# 11_MCU.net
KiCad netlist of a schematic drawn in Altium Designer
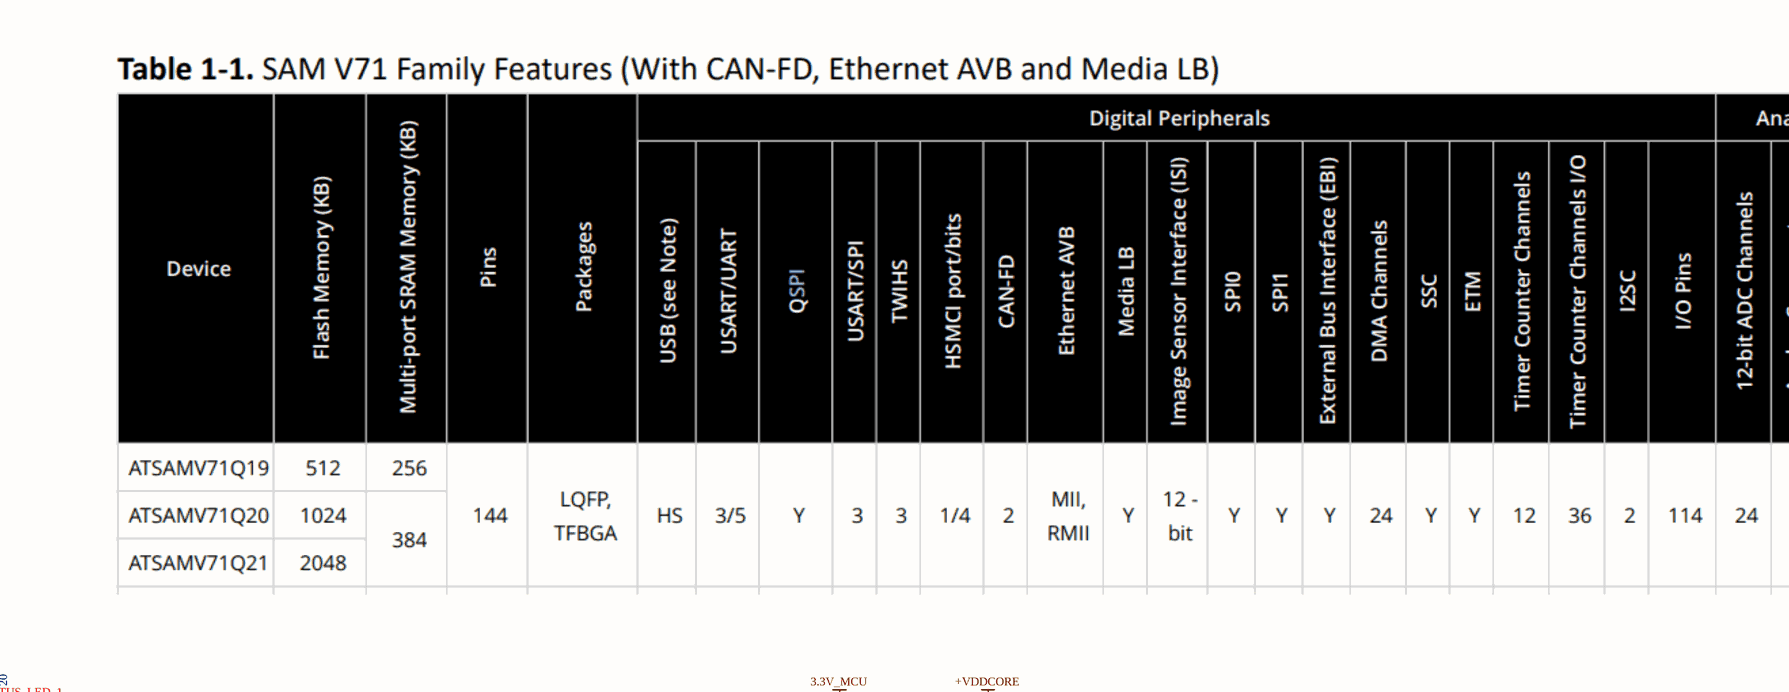
[diagram p0: 11_MCU.SchDoc, top left]
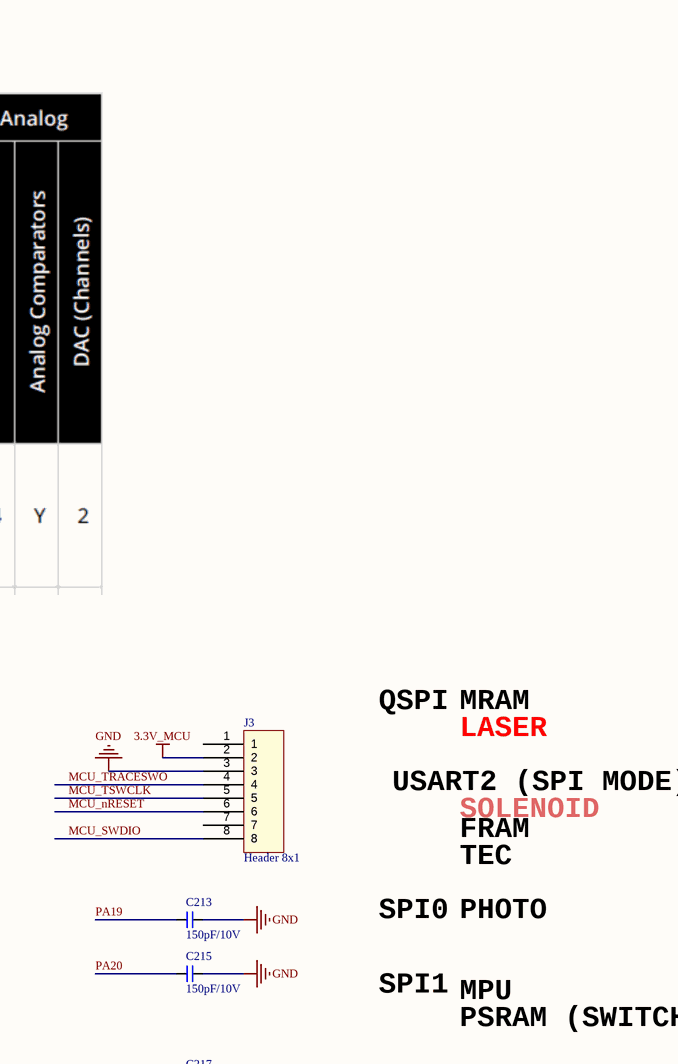
[diagram p1: 11_MCU.SchDoc, top right]
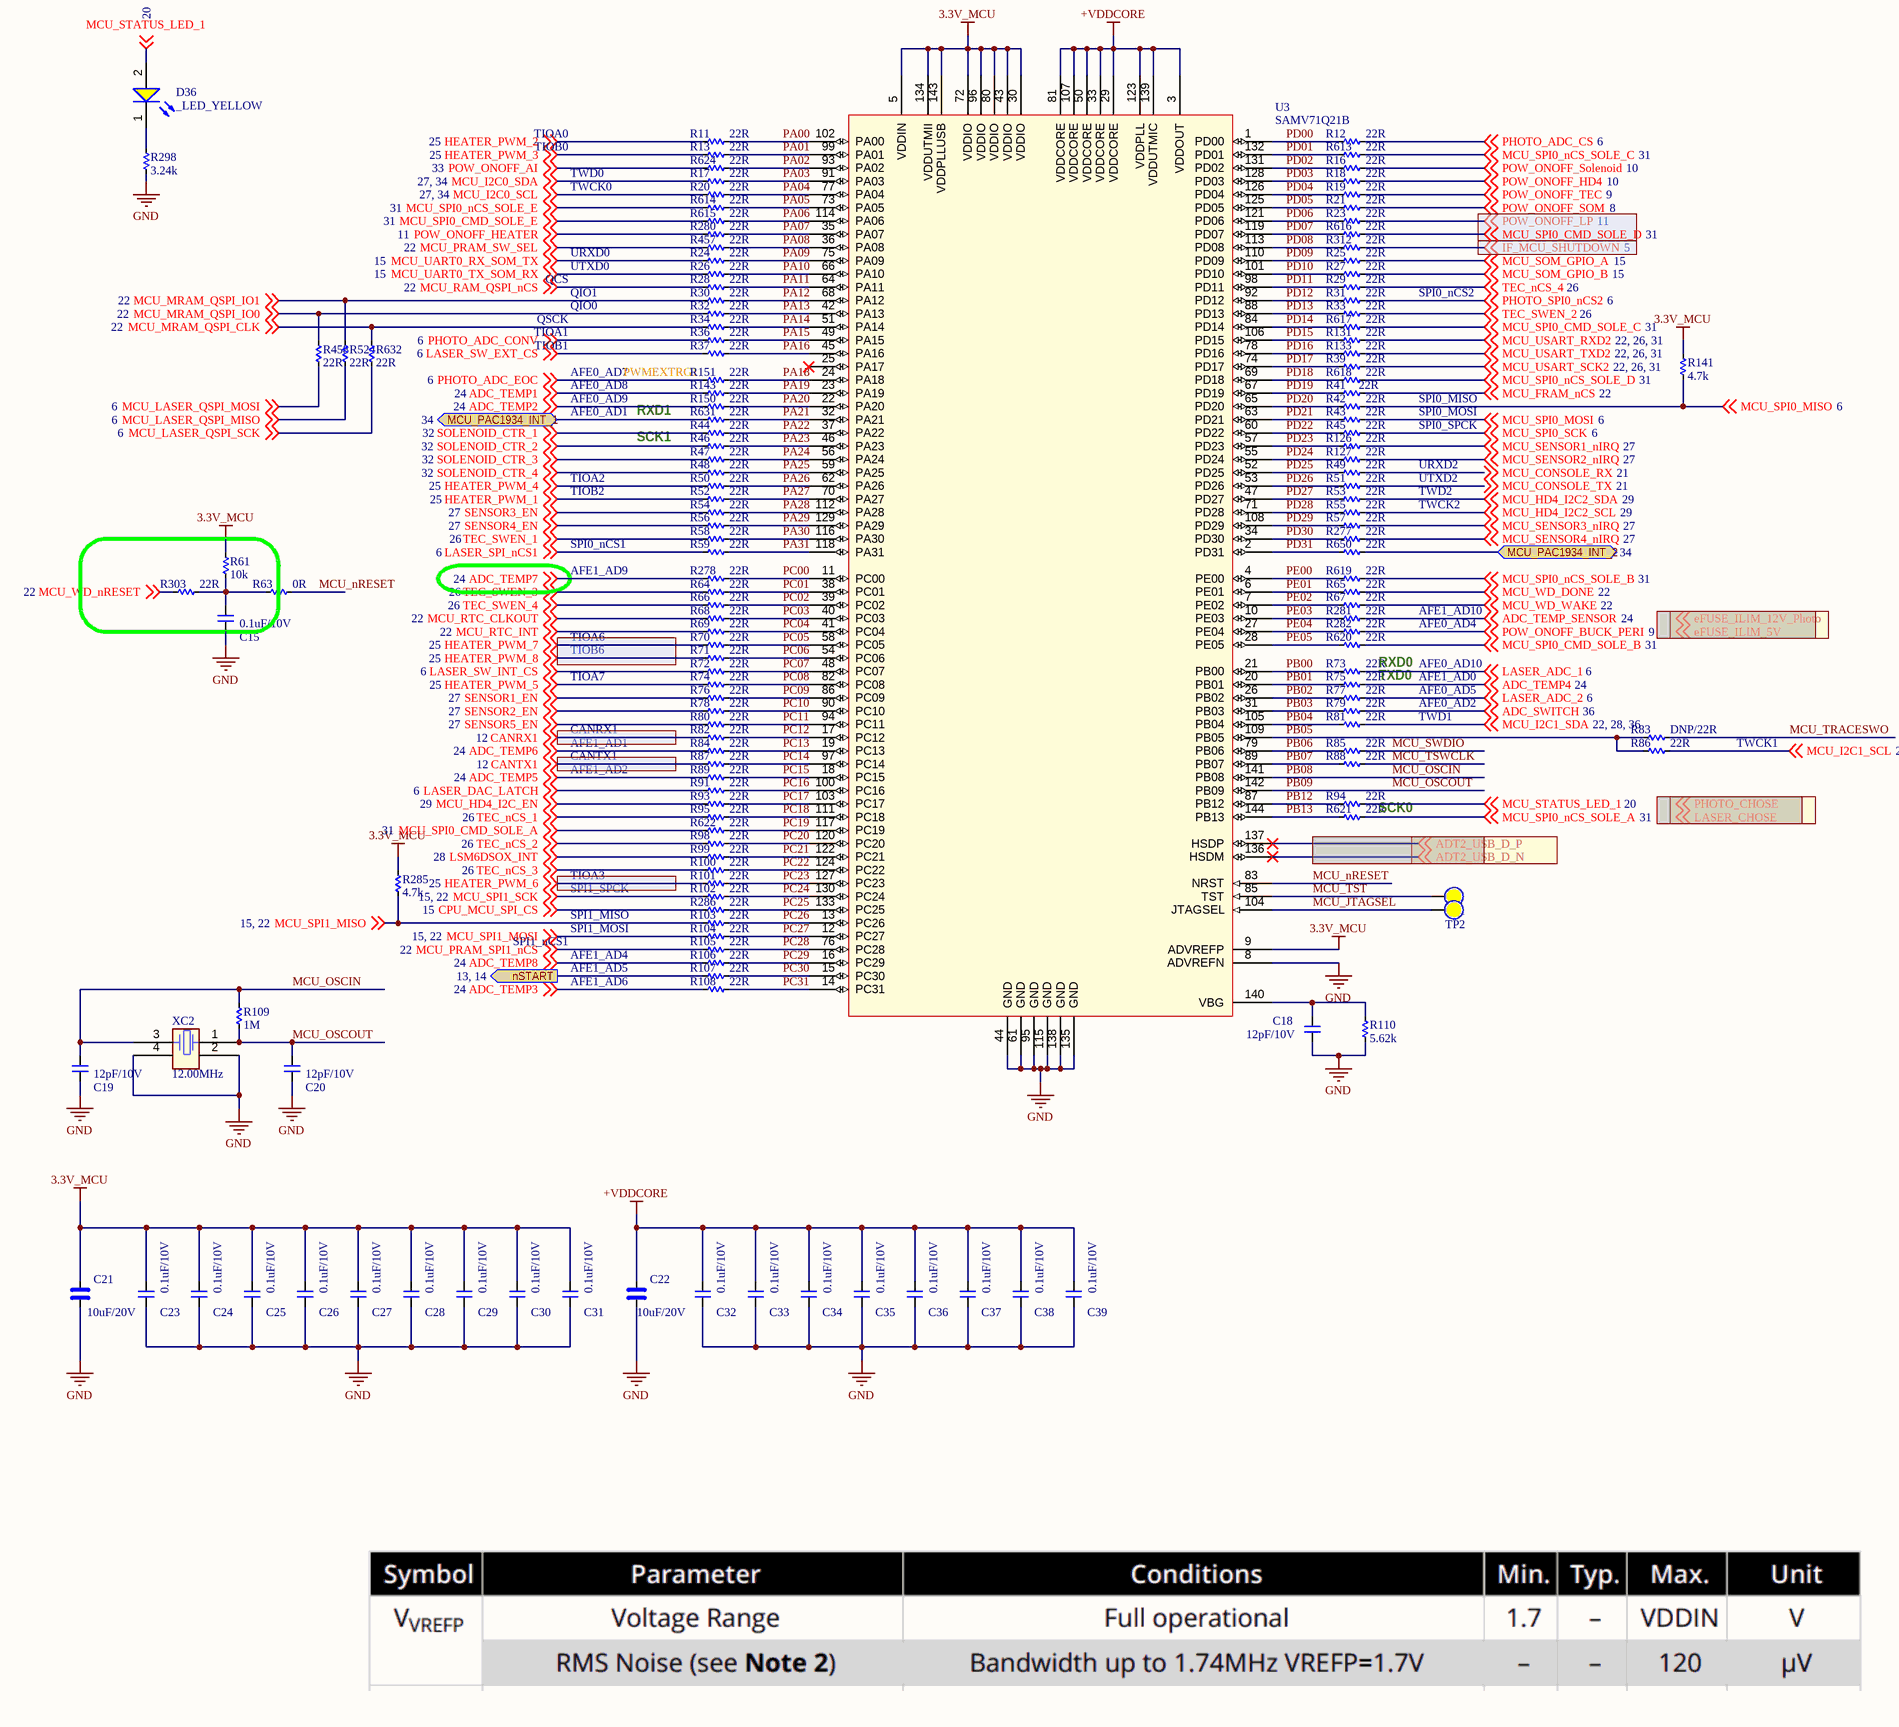
[diagram p2: 11_MCU.SchDoc, bottom left]
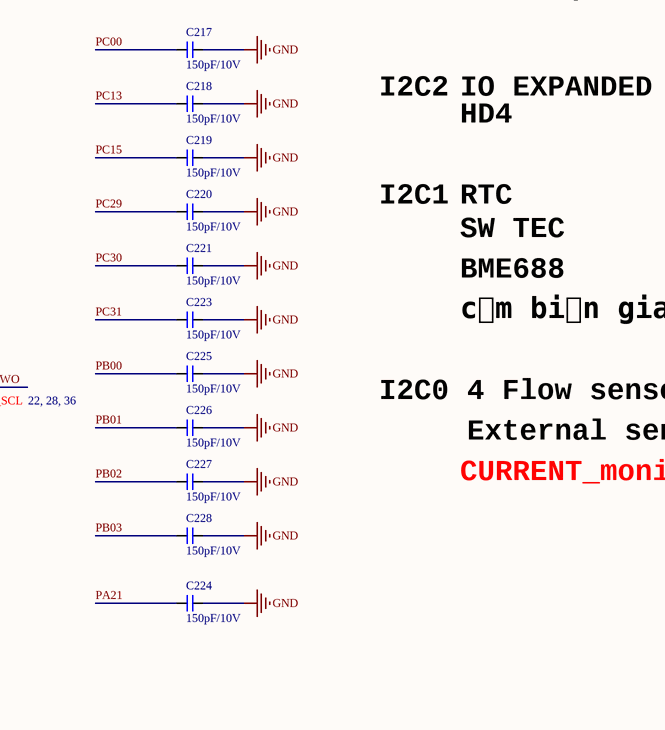
[diagram p3: 11_MCU.SchDoc, bottom right]

(export (version "E")
  (design (tool "Eeschema 10.0.6"))
  (components
    (comp (ref "C15")
      (value "0.1uF/10V")
      (footprint "CAP_C_1005X60")
      (description "CAP")
      (libsource (lib "LABLIB") (part "_CAP_C_2"))
    )
    (comp (ref "C18")
      (value "12pF/10V")
      (footprint "CAP_C_1005X60")
      (description "CAP")
      (libsource (lib "LABLIB") (part "_CAP_C_2"))
    )
    (comp (ref "C19")
      (value "12pF/10V")
      (footprint "CAP_C_1005X60")
      (description "CAP")
      (libsource (lib "LABLIB") (part "_CAP_C_2"))
    )
    (comp (ref "C20")
      (value "12pF/10V")
      (footprint "CAP_C_1005X60")
      (description "CAP")
      (libsource (lib "LABLIB") (part "_CAP_C_2"))
    )
    (comp (ref "C21")
      (value "10uF/20V")
      (footprint "CAP_C_2012X110")
      (description "CAP High Value")
      (libsource (lib "LABLIB") (part "_CAP_C_High_2"))
    )
    (comp (ref "C22")
      (value "10uF/20V")
      (footprint "CAP_C_2012X110")
      (description "CAP High Value")
      (libsource (lib "LABLIB") (part "_CAP_C_High_2"))
    )
    (comp (ref "C23")
      (value "0.1uF/10V")
      (footprint "CAP_C_1005X60")
      (description "CAP")
      (libsource (lib "LABLIB") (part "_CAP_C_2"))
    )
    (comp (ref "C24")
      (value "0.1uF/10V")
      (footprint "CAP_C_1005X60")
      (description "CAP")
      (libsource (lib "LABLIB") (part "_CAP_C_2"))
    )
    (comp (ref "C25")
      (value "0.1uF/10V")
      (footprint "CAP_C_1005X60")
      (description "CAP")
      (libsource (lib "LABLIB") (part "_CAP_C_2"))
    )
    (comp (ref "C26")
      (value "0.1uF/10V")
      (footprint "CAP_C_1005X60")
      (description "CAP")
      (libsource (lib "LABLIB") (part "_CAP_C_2"))
    )
    (comp (ref "C27")
      (value "0.1uF/10V")
      (footprint "CAP_C_1005X60")
      (description "CAP")
      (libsource (lib "LABLIB") (part "_CAP_C_2"))
    )
    (comp (ref "C28")
      (value "0.1uF/10V")
      (footprint "CAP_C_1005X60")
      (description "CAP")
      (libsource (lib "LABLIB") (part "_CAP_C_2"))
    )
    (comp (ref "C29")
      (value "0.1uF/10V")
      (footprint "CAP_C_1005X60")
      (description "CAP")
      (libsource (lib "LABLIB") (part "_CAP_C_2"))
    )
    (comp (ref "C30")
      (value "0.1uF/10V")
      (footprint "CAP_C_1005X60")
      (description "CAP")
      (libsource (lib "LABLIB") (part "_CAP_C_2"))
    )
    (comp (ref "C31")
      (value "0.1uF/10V")
      (footprint "CAP_C_1005X60")
      (description "CAP")
      (libsource (lib "LABLIB") (part "_CAP_C_2"))
    )
    (comp (ref "C32")
      (value "0.1uF/10V")
      (footprint "CAP_C_1005X60")
      (description "CAP")
      (libsource (lib "LABLIB") (part "_CAP_C_2"))
    )
    (comp (ref "C33")
      (value "0.1uF/10V")
      (footprint "CAP_C_1005X60")
      (description "CAP")
      (libsource (lib "LABLIB") (part "_CAP_C_2"))
    )
    (comp (ref "C34")
      (value "0.1uF/10V")
      (footprint "CAP_C_1005X60")
      (description "CAP")
      (libsource (lib "LABLIB") (part "_CAP_C_2"))
    )
    (comp (ref "C35")
      (value "0.1uF/10V")
      (footprint "CAP_C_1005X60")
      (description "CAP")
      (libsource (lib "LABLIB") (part "_CAP_C_2"))
    )
    (comp (ref "C36")
      (value "0.1uF/10V")
      (footprint "CAP_C_1005X60")
      (description "CAP")
      (libsource (lib "LABLIB") (part "_CAP_C_2"))
    )
    (comp (ref "C37")
      (value "0.1uF/10V")
      (footprint "CAP_C_1005X60")
      (description "CAP")
      (libsource (lib "LABLIB") (part "_CAP_C_2"))
    )
    (comp (ref "C38")
      (value "0.1uF/10V")
      (footprint "CAP_C_1005X60")
      (description "CAP")
      (libsource (lib "LABLIB") (part "_CAP_C_2"))
    )
    (comp (ref "C39")
      (value "0.1uF/10V")
      (footprint "CAP_C_1005X60")
      (description "CAP")
      (libsource (lib "LABLIB") (part "_CAP_C_2"))
    )
    (comp (ref "C213")
      (value "150pF/10V")
      (footprint "CAP_C_1005X60")
      (description "CAP")
      (libsource (lib "LABLIB") (part "_CAP_C_2"))
    )
    (comp (ref "C215")
      (value "150pF/10V")
      (footprint "CAP_C_1005X60")
      (description "CAP")
      (libsource (lib "LABLIB") (part "_CAP_C_2"))
    )
    (comp (ref "C217")
      (value "150pF/10V")
      (footprint "CAP_C_1005X60")
      (description "CAP")
      (libsource (lib "LABLIB") (part "_CAP_C_2"))
    )
    (comp (ref "C218")
      (value "150pF/10V")
      (footprint "CAP_C_1005X60")
      (description "CAP")
      (libsource (lib "LABLIB") (part "_CAP_C_2"))
    )
    (comp (ref "C219")
      (value "150pF/10V")
      (footprint "CAP_C_1005X60")
      (description "CAP")
      (libsource (lib "LABLIB") (part "_CAP_C_2"))
    )
    (comp (ref "C220")
      (value "150pF/10V")
      (footprint "CAP_C_1005X60")
      (description "CAP")
      (libsource (lib "LABLIB") (part "_CAP_C_2"))
    )
    (comp (ref "C221")
      (value "150pF/10V")
      (footprint "CAP_C_1005X60")
      (description "CAP")
      (libsource (lib "LABLIB") (part "_CAP_C_2"))
    )
    (comp (ref "C223")
      (value "150pF/10V")
      (footprint "CAP_C_1005X60")
      (description "CAP")
      (libsource (lib "LABLIB") (part "_CAP_C_2"))
    )
    (comp (ref "C224")
      (value "150pF/10V")
      (footprint "CAP_C_1005X60")
      (description "CAP")
      (libsource (lib "LABLIB") (part "_CAP_C_2"))
    )
    (comp (ref "C225")
      (value "150pF/10V")
      (footprint "CAP_C_1005X60")
      (description "CAP")
      (libsource (lib "LABLIB") (part "_CAP_C_2"))
    )
    (comp (ref "C226")
      (value "150pF/10V")
      (footprint "CAP_C_1005X60")
      (description "CAP")
      (libsource (lib "LABLIB") (part "_CAP_C_2"))
    )
    (comp (ref "C227")
      (value "150pF/10V")
      (footprint "CAP_C_1005X60")
      (description "CAP")
      (libsource (lib "LABLIB") (part "_CAP_C_2"))
    )
    (comp (ref "C228")
      (value "150pF/10V")
      (footprint "CAP_C_1005X60")
      (description "CAP")
      (libsource (lib "LABLIB") (part "_CAP_C_2"))
    )
    (comp (ref "D36")
      (value "_LED_YELLOW")
      (footprint "LED_0603")
      (libsource (lib "LABLIB") (part "_LED_YELLOW"))
    )
    (comp (ref "J3")
      (value "Header 8x1")
      (footprint "Header_254P_8x1")
      (libsource (lib "LABLIB") (part "Header 8x1"))
    )
    (comp (ref "R11")
      (value "22R")
      (footprint "RES_C_1005X40")
      (description "RES")
      (libsource (lib "LABLIB") (part "_RES_B_2"))
    )
    (comp (ref "R12")
      (value "22R")
      (footprint "RES_C_1005X40")
      (description "RES")
      (libsource (lib "LABLIB") (part "_RES_B_2"))
    )
    (comp (ref "R13")
      (value "22R")
      (footprint "RES_C_1005X40")
      (description "RES")
      (libsource (lib "LABLIB") (part "_RES_B_2"))
    )
    (comp (ref "R16")
      (value "22R")
      (footprint "RES_C_1005X40")
      (description "RES")
      (libsource (lib "LABLIB") (part "_RES_B_2"))
    )
    (comp (ref "R17")
      (value "22R")
      (footprint "RES_C_1005X40")
      (description "RES")
      (libsource (lib "LABLIB") (part "_RES_B_2"))
    )
    (comp (ref "R18")
      (value "22R")
      (footprint "RES_C_1005X40")
      (description "RES")
      (libsource (lib "LABLIB") (part "_RES_B_2"))
    )
    (comp (ref "R19")
      (value "22R")
      (footprint "RES_C_1005X40")
      (description "RES")
      (libsource (lib "LABLIB") (part "_RES_B_2"))
    )
    (comp (ref "R20")
      (value "22R")
      (footprint "RES_C_1005X40")
      (description "RES")
      (libsource (lib "LABLIB") (part "_RES_B_2"))
    )
    (comp (ref "R21")
      (value "22R")
      (footprint "RES_C_1005X40")
      (description "RES")
      (libsource (lib "LABLIB") (part "_RES_B_2"))
    )
    (comp (ref "R23")
      (value "22R")
      (footprint "RES_C_1005X40")
      (description "RES")
      (libsource (lib "LABLIB") (part "_RES_B_2"))
    )
    (comp (ref "R24")
      (value "22R")
      (footprint "RES_C_1005X40")
      (description "RES")
      (libsource (lib "LABLIB") (part "_RES_B_2"))
    )
    (comp (ref "R25")
      (value "22R")
      (footprint "RES_C_1005X40")
      (description "RES")
      (libsource (lib "LABLIB") (part "_RES_B_2"))
    )
    (comp (ref "R26")
      (value "22R")
      (footprint "RES_C_1005X40")
      (description "RES")
      (libsource (lib "LABLIB") (part "_RES_B_2"))
    )
    (comp (ref "R27")
      (value "22R")
      (footprint "RES_C_1005X40")
      (description "RES")
      (libsource (lib "LABLIB") (part "_RES_B_2"))
    )
    (comp (ref "R28")
      (value "22R")
      (footprint "RES_C_1005X40")
      (description "RES")
      (libsource (lib "LABLIB") (part "_RES_B_2"))
    )
    (comp (ref "R29")
      (value "22R")
      (footprint "RES_C_1005X40")
      (description "RES")
      (libsource (lib "LABLIB") (part "_RES_B_2"))
    )
    (comp (ref "R30")
      (value "22R")
      (footprint "RES_C_1005X40")
      (description "RES")
      (libsource (lib "LABLIB") (part "_RES_B_2"))
    )
    (comp (ref "R31")
      (value "22R")
      (footprint "RES_C_1005X40")
      (description "RES")
      (libsource (lib "LABLIB") (part "_RES_B_2"))
    )
    (comp (ref "R32")
      (value "22R")
      (footprint "RES_C_1005X40")
      (description "RES")
      (libsource (lib "LABLIB") (part "_RES_B_2"))
    )
    (comp (ref "R33")
      (value "22R")
      (footprint "RES_C_1005X40")
      (description "RES")
      (libsource (lib "LABLIB") (part "_RES_B_2"))
    )
    (comp (ref "R34")
      (value "22R")
      (footprint "RES_C_1005X40")
      (description "RES")
      (libsource (lib "LABLIB") (part "_RES_B_2"))
    )
    (comp (ref "R36")
      (value "22R")
      (footprint "RES_C_1005X40")
      (description "RES")
      (libsource (lib "LABLIB") (part "_RES_B_2"))
    )
    (comp (ref "R37")
      (value "22R")
      (footprint "RES_C_1005X40")
      (description "RES")
      (libsource (lib "LABLIB") (part "_RES_B_2"))
    )
    (comp (ref "R39")
      (value "22R")
      (footprint "RES_C_1005X40")
      (description "RES")
      (libsource (lib "LABLIB") (part "_RES_B_2"))
    )
    (comp (ref "R41")
      (value "22R")
      (footprint "RES_C_1005X40")
      (description "RES")
      (libsource (lib "LABLIB") (part "_RES_B_2"))
    )
    (comp (ref "R42")
      (value "22R")
      (footprint "RES_C_1005X40")
      (description "RES")
      (libsource (lib "LABLIB") (part "_RES_B_2"))
    )
    (comp (ref "R43")
      (value "22R")
      (footprint "RES_C_1005X40")
      (description "RES")
      (libsource (lib "LABLIB") (part "_RES_B_2"))
    )
    (comp (ref "R44")
      (value "22R")
      (footprint "RES_C_1005X40")
      (description "RES")
      (libsource (lib "LABLIB") (part "_RES_B_2"))
    )
    (comp (ref "R45")
      (value "22R")
      (footprint "RES_C_1005X40")
      (description "RES")
      (libsource (lib "LABLIB") (part "_RES_B_2"))
    )
    (comp (ref "R46")
      (value "22R")
      (footprint "RES_C_1005X40")
      (description "RES")
      (libsource (lib "LABLIB") (part "_RES_B_2"))
    )
    (comp (ref "R47")
      (value "22R")
      (footprint "RES_C_1005X40")
      (description "RES")
      (libsource (lib "LABLIB") (part "_RES_B_2"))
    )
    (comp (ref "R48")
      (value "22R")
      (footprint "RES_C_1005X40")
      (description "RES")
      (libsource (lib "LABLIB") (part "_RES_B_2"))
    )
    (comp (ref "R49")
      (value "22R")
      (footprint "RES_C_1005X40")
      (description "RES")
      (libsource (lib "LABLIB") (part "_RES_B_2"))
    )
    (comp (ref "R50")
      (value "22R")
      (footprint "RES_C_1005X40")
      (description "RES")
      (libsource (lib "LABLIB") (part "_RES_B_2"))
    )
    (comp (ref "R51")
      (value "22R")
      (footprint "RES_C_1005X40")
      (description "RES")
      (libsource (lib "LABLIB") (part "_RES_B_2"))
    )
    (comp (ref "R52")
      (value "22R")
      (footprint "RES_C_1005X40")
      (description "RES")
      (libsource (lib "LABLIB") (part "_RES_B_2"))
    )
    (comp (ref "R53")
      (value "22R")
      (footprint "RES_C_1005X40")
      (description "RES")
      (libsource (lib "LABLIB") (part "_RES_B_2"))
    )
    (comp (ref "R54")
      (value "22R")
      (footprint "RES_C_1005X40")
      (description "RES")
      (libsource (lib "LABLIB") (part "_RES_B_2"))
    )
    (comp (ref "R55")
      (value "22R")
      (footprint "RES_C_1005X40")
      (description "RES")
      (libsource (lib "LABLIB") (part "_RES_B_2"))
    )
    (comp (ref "R56")
      (value "22R")
      (footprint "RES_C_1005X40")
      (description "RES")
      (libsource (lib "LABLIB") (part "_RES_B_2"))
    )
    (comp (ref "R57")
      (value "22R")
      (footprint "RES_C_1005X40")
      (description "RES")
      (libsource (lib "LABLIB") (part "_RES_B_2"))
    )
    (comp (ref "R58")
      (value "22R")
      (footprint "RES_C_1005X40")
      (description "RES")
      (libsource (lib "LABLIB") (part "_RES_B_2"))
    )
    (comp (ref "R59")
      (value "22R")
      (footprint "RES_C_1005X40")
      (description "RES")
      (libsource (lib "LABLIB") (part "_RES_B_2"))
    )
    (comp (ref "R61")
      (value "10k")
      (footprint "RES_C_1005X40")
      (description "RES")
      (libsource (lib "LABLIB") (part "_RES_B_2"))
    )
    (comp (ref "R63")
      (value "0R")
      (footprint "RES_C_1005X40")
      (description "RES")
      (libsource (lib "LABLIB") (part "_RES_B_2"))
    )
    (comp (ref "R64")
      (value "22R")
      (footprint "RES_C_1005X40")
      (description "RES")
      (libsource (lib "LABLIB") (part "_RES_B_2"))
    )
    (comp (ref "R65")
      (value "22R")
      (footprint "RES_C_1005X40")
      (description "RES")
      (libsource (lib "LABLIB") (part "_RES_B_2"))
    )
    (comp (ref "R66")
      (value "22R")
      (footprint "RES_C_1005X40")
      (description "RES")
      (libsource (lib "LABLIB") (part "_RES_B_2"))
    )
    (comp (ref "R67")
      (value "22R")
      (footprint "RES_C_1005X40")
      (description "RES")
      (libsource (lib "LABLIB") (part "_RES_B_2"))
    )
    (comp (ref "R68")
      (value "22R")
      (footprint "RES_C_1005X40")
      (description "RES")
      (libsource (lib "LABLIB") (part "_RES_B_2"))
    )
    (comp (ref "R69")
      (value "22R")
      (footprint "RES_C_1005X40")
      (description "RES")
      (libsource (lib "LABLIB") (part "_RES_B_2"))
    )
    (comp (ref "R70")
      (value "22R")
      (footprint "RES_C_1005X40")
      (description "RES")
      (libsource (lib "LABLIB") (part "_RES_B_2"))
    )
    (comp (ref "R71")
      (value "22R")
      (footprint "RES_C_1005X40")
      (description "RES")
      (libsource (lib "LABLIB") (part "_RES_B_2"))
    )
    (comp (ref "R72")
      (value "22R")
      (footprint "RES_C_1005X40")
      (description "RES")
      (libsource (lib "LABLIB") (part "_RES_B_2"))
    )
    (comp (ref "R73")
      (value "22R")
      (footprint "RES_C_1005X40")
      (description "RES")
      (libsource (lib "LABLIB") (part "_RES_B_2"))
    )
    (comp (ref "R74")
      (value "22R")
      (footprint "RES_C_1005X40")
      (description "RES")
      (libsource (lib "LABLIB") (part "_RES_B_2"))
    )
    (comp (ref "R75")
      (value "22R")
      (footprint "RES_C_1005X40")
      (description "RES")
      (libsource (lib "LABLIB") (part "_RES_B_2"))
    )
    (comp (ref "R76")
      (value "22R")
      (footprint "RES_C_1005X40")
      (description "RES")
      (libsource (lib "LABLIB") (part "_RES_B_2"))
    )
    (comp (ref "R77")
      (value "22R")
      (footprint "RES_C_1005X40")
      (description "RES")
      (libsource (lib "LABLIB") (part "_RES_B_2"))
    )
    (comp (ref "R78")
      (value "22R")
      (footprint "RES_C_1005X40")
      (description "RES")
      (libsource (lib "LABLIB") (part "_RES_B_2"))
    )
    (comp (ref "R79")
      (value "22R")
      (footprint "RES_C_1005X40")
      (description "RES")
      (libsource (lib "LABLIB") (part "_RES_B_2"))
    )
    (comp (ref "R80")
      (value "22R")
      (footprint "RES_C_1005X40")
      (description "RES")
      (libsource (lib "LABLIB") (part "_RES_B_2"))
    )
    (comp (ref "R81")
      (value "22R")
      (footprint "RES_C_1005X40")
      (description "RES")
      (libsource (lib "LABLIB") (part "_RES_B_2"))
    )
    (comp (ref "R82")
      (value "22R")
      (footprint "RES_C_1005X40")
      (description "RES")
      (libsource (lib "LABLIB") (part "_RES_B_2"))
    )
    (comp (ref "R83")
      (value "DNP/22R")
      (footprint "RES_C_1005X40")
      (description "RES")
      (libsource (lib "LABLIB") (part "_RES_B_2"))
    )
    (comp (ref "R84")
      (value "22R")
      (footprint "RES_C_1005X40")
      (description "RES")
      (libsource (lib "LABLIB") (part "_RES_B_2"))
    )
    (comp (ref "R85")
      (value "22R")
      (footprint "RES_C_1005X40")
      (description "RES")
      (libsource (lib "LABLIB") (part "_RES_B_2"))
    )
    (comp (ref "R86")
      (value "22R")
      (footprint "RES_C_1005X40")
      (description "RES")
      (libsource (lib "LABLIB") (part "_RES_B_2"))
    )
    (comp (ref "R87")
      (value "22R")
      (footprint "RES_C_1005X40")
      (description "RES")
      (libsource (lib "LABLIB") (part "_RES_B_2"))
    )
    (comp (ref "R88")
      (value "22R")
      (footprint "RES_C_1005X40")
      (description "RES")
      (libsource (lib "LABLIB") (part "_RES_B_2"))
    )
    (comp (ref "R89")
      (value "22R")
      (footprint "RES_C_1005X40")
      (description "RES")
      (libsource (lib "LABLIB") (part "_RES_B_2"))
    )
    (comp (ref "R91")
      (value "22R")
      (footprint "RES_C_1005X40")
      (description "RES")
      (libsource (lib "LABLIB") (part "_RES_B_2"))
    )
    (comp (ref "R93")
      (value "22R")
      (footprint "RES_C_1005X40")
      (description "RES")
      (libsource (lib "LABLIB") (part "_RES_B_2"))
    )
    (comp (ref "R94")
      (value "22R")
      (footprint "RES_C_1005X40")
      (description "RES")
      (libsource (lib "LABLIB") (part "_RES_B_2"))
    )
    (comp (ref "R95")
      (value "22R")
      (footprint "RES_C_1005X40")
      (description "RES")
      (libsource (lib "LABLIB") (part "_RES_B_2"))
    )
    (comp (ref "R98")
      (value "22R")
      (footprint "RES_C_1005X40")
      (description "RES")
      (libsource (lib "LABLIB") (part "_RES_B_2"))
    )
    (comp (ref "R99")
      (value "22R")
      (footprint "RES_C_1005X40")
      (description "RES")
      (libsource (lib "LABLIB") (part "_RES_B_2"))
    )
    (comp (ref "R100")
      (value "22R")
      (footprint "RES_C_1005X40")
      (description "RES")
      (libsource (lib "LABLIB") (part "_RES_B_2"))
    )
    (comp (ref "R101")
      (value "22R")
      (footprint "RES_C_1005X40")
      (description "RES")
      (libsource (lib "LABLIB") (part "_RES_B_2"))
    )
    (comp (ref "R102")
      (value "22R")
      (footprint "RES_C_1005X40")
      (description "RES")
      (libsource (lib "LABLIB") (part "_RES_B_2"))
    )
    (comp (ref "R103")
      (value "22R")
      (footprint "RES_C_1005X40")
      (description "RES")
      (libsource (lib "LABLIB") (part "_RES_B_2"))
    )
    (comp (ref "R104")
      (value "22R")
      (footprint "RES_C_1005X40")
      (description "RES")
      (libsource (lib "LABLIB") (part "_RES_B_2"))
    )
    (comp (ref "R105")
      (value "22R")
      (footprint "RES_C_1005X40")
      (description "RES")
      (libsource (lib "LABLIB") (part "_RES_B_2"))
    )
    (comp (ref "R106")
      (value "22R")
      (footprint "RES_C_1005X40")
      (description "RES")
      (libsource (lib "LABLIB") (part "_RES_B_2"))
    )
    (comp (ref "R107")
      (value "22R")
      (footprint "RES_C_1005X40")
      (description "RES")
      (libsource (lib "LABLIB") (part "_RES_B_2"))
    )
    (comp (ref "R108")
      (value "22R")
      (footprint "RES_C_1005X40")
      (description "RES")
      (libsource (lib "LABLIB") (part "_RES_B_2"))
    )
    (comp (ref "R109")
      (value "1M")
      (footprint "RES_C_1005X40")
      (description "RES")
      (libsource (lib "LABLIB") (part "_RES_B_2"))
    )
    (comp (ref "R110")
      (value "5.62k")
      (footprint "RES_C_1005X40")
      (description "RES")
      (libsource (lib "LABLIB") (part "_RES_B_2"))
    )
    (comp (ref "R126")
      (value "22R")
      (footprint "RES_C_1005X40")
      (description "RES")
      (libsource (lib "LABLIB") (part "_RES_B_2"))
    )
    (comp (ref "R127")
      (value "22R")
      (footprint "RES_C_1005X40")
      (description "RES")
      (libsource (lib "LABLIB") (part "_RES_B_2"))
    )
    (comp (ref "R131")
      (value "22R")
      (footprint "RES_C_1005X40")
      (description "RES")
      (libsource (lib "LABLIB") (part "_RES_B_2"))
    )
    (comp (ref "R133")
      (value "22R")
      (footprint "RES_C_1005X40")
      (description "RES")
      (libsource (lib "LABLIB") (part "_RES_B_2"))
    )
    (comp (ref "R141")
      (value "4.7k")
      (footprint "RES_C_1005X40")
      (description "RES")
      (libsource (lib "LABLIB") (part "_RES_B_2"))
    )
    (comp (ref "R143")
      (value "22R")
      (footprint "RES_C_1005X40")
      (description "RES")
      (libsource (lib "LABLIB") (part "_RES_B_2"))
    )
    (comp (ref "R150")
      (value "22R")
      (footprint "RES_C_1005X40")
      (description "RES")
      (libsource (lib "LABLIB") (part "_RES_B_2"))
    )
    (comp (ref "R151")
      (value "22R")
      (footprint "RES_C_1005X40")
      (description "RES")
      (libsource (lib "LABLIB") (part "_RES_B_2"))
    )
    (comp (ref "R277")
      (value "22R")
      (footprint "RES_C_1005X40")
      (description "RES")
      (libsource (lib "LABLIB") (part "_RES_B_2"))
    )
    (comp (ref "R278")
      (value "22R")
      (footprint "RES_C_1005X40")
      (description "RES")
      (libsource (lib "LABLIB") (part "_RES_B_2"))
    )
    (comp (ref "R280")
      (value "22R")
      (footprint "RES_C_1005X40")
      (description "RES")
      (libsource (lib "LABLIB") (part "_RES_B_2"))
    )
    (comp (ref "R281")
      (value "22R")
      (footprint "RES_C_1005X40")
      (description "RES")
      (libsource (lib "LABLIB") (part "_RES_B_2"))
    )
    (comp (ref "R282")
      (value "22R")
      (footprint "RES_C_1005X40")
      (description "RES")
      (libsource (lib "LABLIB") (part "_RES_B_2"))
    )
    (comp (ref "R285")
      (value "4.7k")
      (footprint "RES_C_1005X40")
      (description "RES")
      (libsource (lib "LABLIB") (part "_RES_B_2"))
    )
    (comp (ref "R286")
      (value "22R")
      (footprint "RES_C_1005X40")
      (description "RES")
      (libsource (lib "LABLIB") (part "_RES_B_2"))
    )
    (comp (ref "R298")
      (value "3.24k")
      (footprint "RES_C_1005X40")
      (description "RES")
      (libsource (lib "LABLIB") (part "_RES_B_2"))
    )
    (comp (ref "R303")
      (value "22R")
      (footprint "RES_C_1005X40")
      (description "RES")
      (libsource (lib "LABLIB") (part "_RES_B_2"))
    )
    (comp (ref "R312")
      (value "22R")
      (footprint "RES_C_1005X40")
      (description "RES")
      (libsource (lib "LABLIB") (part "_RES_B_2"))
    )
    (comp (ref "R457")
      (value "22R")
      (footprint "RES_C_1005X40")
      (description "RES")
      (libsource (lib "LABLIB") (part "_RES_B_2"))
    )
    (comp (ref "R458")
      (value "22R")
      (footprint "RES_C_1005X40")
      (description "RES")
      (libsource (lib "LABLIB") (part "_RES_B_2"))
    )
    (comp (ref "R524")
      (value "22R")
      (footprint "RES_C_1005X40")
      (description "RES")
      (libsource (lib "LABLIB") (part "_RES_B_2"))
    )
    (comp (ref "R613")
      (value "22R")
      (footprint "RES_C_1005X40")
      (description "RES")
      (libsource (lib "LABLIB") (part "_RES_B_2"))
    )
    (comp (ref "R614")
      (value "22R")
      (footprint "RES_C_1005X40")
      (description "RES")
      (libsource (lib "LABLIB") (part "_RES_B_2"))
    )
    (comp (ref "R615")
      (value "22R")
      (footprint "RES_C_1005X40")
      (description "RES")
      (libsource (lib "LABLIB") (part "_RES_B_2"))
    )
    (comp (ref "R616")
      (value "22R")
      (footprint "RES_C_1005X40")
      (description "RES")
      (libsource (lib "LABLIB") (part "_RES_B_2"))
    )
    (comp (ref "R617")
      (value "22R")
      (footprint "RES_C_1005X40")
      (description "RES")
      (libsource (lib "LABLIB") (part "_RES_B_2"))
    )
    (comp (ref "R618")
      (value "22R")
      (footprint "RES_C_1005X40")
      (description "RES")
      (libsource (lib "LABLIB") (part "_RES_B_2"))
    )
    (comp (ref "R619")
      (value "22R")
      (footprint "RES_C_1005X40")
      (description "RES")
      (libsource (lib "LABLIB") (part "_RES_B_2"))
    )
    (comp (ref "R620")
      (value "22R")
      (footprint "RES_C_1005X40")
      (description "RES")
      (libsource (lib "LABLIB") (part "_RES_B_2"))
    )
    (comp (ref "R621")
      (value "22R")
      (footprint "RES_C_1005X40")
      (description "RES")
      (libsource (lib "LABLIB") (part "_RES_B_2"))
    )
    (comp (ref "R622")
      (value "22R")
      (footprint "RES_C_1005X40")
      (description "RES")
      (libsource (lib "LABLIB") (part "_RES_B_2"))
    )
    (comp (ref "R624")
      (value "22R")
      (footprint "RES_C_1005X40")
      (description "RES")
      (libsource (lib "LABLIB") (part "_RES_B_2"))
    )
    (comp (ref "R631")
      (value "22R")
      (footprint "RES_C_1005X40")
      (description "RES")
      (libsource (lib "LABLIB") (part "_RES_B_2"))
    )
    (comp (ref "R632")
      (value "22R")
      (footprint "RES_C_1005X40")
      (description "RES")
      (libsource (lib "LABLIB") (part "_RES_B_2"))
    )
    (comp (ref "R650")
      (value "22R")
      (footprint "RES_C_1005X40")
      (description "RES")
      (libsource (lib "LABLIB") (part "_RES_B_2"))
    )
    (comp (ref "TP1")
      (value "~")
      (footprint "Testpoint_80")
      (description "Test Point")
      (libsource (lib "LABLIB") (part "Test Point"))
    )
    (comp (ref "TP2")
      (value "~")
      (footprint "Testpoint_80")
      (description "Test Point")
      (libsource (lib "LABLIB") (part "Test Point"))
    )
    (comp (ref "U3")
      (value "SAMV71Q21B")
      (footprint "AP6-00118")
      (description "SAM 32-bit ARM Cortex-M* RISC MCU, SAMV71B Series, QFP144")
      (fields (field (name "MANUFACTURER") "MICROCHIP") (field (name "MPN") "ATSAMV71Q21B-AAB"))
      (libsource (lib "AltiumDbLib") (part "SAMV7_LQFP144"))
    )
    (comp (ref "XC2")
      (value "12.00MHz")
      (footprint "AP7-00039")
      (description "Fox FQ5032B 12.0MHz SMD crystal 738B-12")
      (fields (field (name "TOLERANCE") "Â±30ppm") (field (name "MANUFACTURER") "Fox  Electronics"))
      (libsource (lib "AltiumDbLib") (part "CRYSTAL1324"))
    )
  )
  (nets
    (net (code "1") (name "+VDDCORE") (class "Default")
      (node (ref "C22") (pin "1") (pinfunction "1_1") (pintype "passive"))
      (node (ref "C32") (pin "2") (pinfunction "2_2") (pintype "passive"))
      (node (ref "C33") (pin "2") (pinfunction "2_2") (pintype "passive"))
      (node (ref "C34") (pin "2") (pinfunction "2_2") (pintype "passive"))
      (node (ref "C35") (pin "2") (pinfunction "2_2") (pintype "passive"))
      (node (ref "C36") (pin "2") (pinfunction "2_2") (pintype "passive"))
      (node (ref "C37") (pin "2") (pinfunction "2_2") (pintype "passive"))
      (node (ref "C38") (pin "2") (pinfunction "2_2") (pintype "passive"))
      (node (ref "C39") (pin "2") (pinfunction "2_2") (pintype "passive"))
      (node (ref "U3") (pin "107") (pinfunction "VDDCORE_107") (pintype "power_in"))
      (node (ref "U3") (pin "123") (pinfunction "VDDPLL_123") (pintype "power_in"))
      (node (ref "U3") (pin "139") (pinfunction "VDDUTMIC_139") (pintype "power_in"))
      (node (ref "U3") (pin "29") (pinfunction "VDDCORE_29") (pintype "power_in"))
      (node (ref "U3") (pin "3") (pinfunction "VDDOUT_3") (pintype "power_in"))
      (node (ref "U3") (pin "33") (pinfunction "VDDCORE_33") (pintype "power_in"))
      (node (ref "U3") (pin "50") (pinfunction "VDDCORE_50") (pintype "power_in"))
      (node (ref "U3") (pin "81") (pinfunction "VDDCORE_81") (pintype "power_in"))
    )
    (net (code "2") (name "/MCU_JTAGSEL") (class "Default")
      (node (ref "TP2") (pin "1") (pinfunction "1_1") (pintype "passive"))
      (node (ref "U3") (pin "104") (pinfunction "JTAGSEL_104") (pintype "input"))
    )
    (net (code "3") (name "/MCU_OSCIN") (class "Default")
      (node (ref "C19") (pin "2") (pinfunction "2_2") (pintype "passive"))
      (node (ref "R109") (pin "2") (pinfunction "2_2") (pintype "passive"))
      (node (ref "U3") (pin "141") (pinfunction "PB08_141") (pintype "bidirectional"))
      (node (ref "XC2") (pin "3") (pinfunction "3_3") (pintype "passive"))
    )
    (net (code "4") (name "/MCU_OSCOUT") (class "Default")
      (node (ref "C20") (pin "2") (pinfunction "2_2") (pintype "passive"))
      (node (ref "R109") (pin "1") (pinfunction "1_1") (pintype "passive"))
      (node (ref "U3") (pin "142") (pinfunction "PB09_142") (pintype "bidirectional"))
      (node (ref "XC2") (pin "1") (pinfunction "1_1") (pintype "passive"))
    )
    (net (code "5") (name "/MCU_PAC1934_INT_1") (class "Default")
      (node (ref "R631") (pin "2") (pinfunction "2_2") (pintype "passive"))
    )
    (net (code "6") (name "/MCU_PAC1934_INT_2") (class "Default")
      (node (ref "R650") (pin "2") (pinfunction "2_2") (pintype "passive"))
    )
    (net (code "7") (name "/MCU_SWDIO") (class "Default")
      (node (ref "J3") (pin "8") (pinfunction "8_8") (pintype "passive"))
      (node (ref "R85") (pin "1") (pinfunction "1_1") (pintype "passive"))
    )
    (net (code "8") (name "/MCU_TRACESWO") (class "Default")
      (node (ref "J3") (pin "4") (pinfunction "4_4") (pintype "passive"))
      (node (ref "R83") (pin "1") (pinfunction "1_1") (pintype "passive"))
    )
    (net (code "9") (name "/MCU_TST") (class "Default")
      (node (ref "TP1") (pin "1") (pinfunction "1_1") (pintype "passive"))
      (node (ref "U3") (pin "85") (pinfunction "TST_85") (pintype "input"))
    )
    (net (code "10") (name "/MCU_TSWCLK") (class "Default")
      (node (ref "J3") (pin "5") (pinfunction "5_5") (pintype "passive"))
      (node (ref "R88") (pin "1") (pinfunction "1_1") (pintype "passive"))
    )
    (net (code "11") (name "/MCU_nRESET") (class "Default")
      (node (ref "J3") (pin "6") (pinfunction "6_6") (pintype "passive"))
      (node (ref "R63") (pin "1") (pinfunction "1_1") (pintype "passive"))
      (node (ref "U3") (pin "83") (pinfunction "NRST_83") (pintype "input"))
    )
    (net (code "12") (name "/PA00") (class "Default")
      (node (ref "R11") (pin "1") (pinfunction "1_1") (pintype "passive"))
      (node (ref "U3") (pin "102") (pinfunction "PA00_102") (pintype "bidirectional"))
    )
    (net (code "13") (name "/PA01") (class "Default")
      (node (ref "R13") (pin "1") (pinfunction "1_1") (pintype "passive"))
      (node (ref "U3") (pin "99") (pinfunction "PA01_99") (pintype "bidirectional"))
    )
    (net (code "14") (name "/PA02") (class "Default")
      (node (ref "R624") (pin "1") (pinfunction "1_1") (pintype "passive"))
      (node (ref "U3") (pin "93") (pinfunction "PA02_93") (pintype "bidirectional"))
    )
    (net (code "15") (name "/PA03") (class "Default")
      (node (ref "R17") (pin "1") (pinfunction "1_1") (pintype "passive"))
      (node (ref "U3") (pin "91") (pinfunction "PA03_91") (pintype "bidirectional"))
    )
    (net (code "16") (name "/PA04") (class "Default")
      (node (ref "R20") (pin "1") (pinfunction "1_1") (pintype "passive"))
      (node (ref "U3") (pin "77") (pinfunction "PA04_77") (pintype "bidirectional"))
    )
    (net (code "17") (name "/PA05") (class "Default")
      (node (ref "R614") (pin "1") (pinfunction "1_1") (pintype "passive"))
      (node (ref "U3") (pin "73") (pinfunction "PA05_73") (pintype "bidirectional"))
    )
    (net (code "18") (name "/PA06") (class "Default")
      (node (ref "R615") (pin "1") (pinfunction "1_1") (pintype "passive"))
      (node (ref "U3") (pin "114") (pinfunction "PA06_114") (pintype "bidirectional"))
    )
    (net (code "19") (name "/PA07") (class "Default")
      (node (ref "R280") (pin "1") (pinfunction "1_1") (pintype "passive"))
      (node (ref "U3") (pin "35") (pinfunction "PA07_35") (pintype "bidirectional"))
    )
    (net (code "20") (name "/PA08") (class "Default")
      (node (ref "R457") (pin "1") (pinfunction "1_1") (pintype "passive"))
      (node (ref "U3") (pin "36") (pinfunction "PA08_36") (pintype "bidirectional"))
    )
    (net (code "21") (name "/PA09") (class "Default")
      (node (ref "R24") (pin "1") (pinfunction "1_1") (pintype "passive"))
      (node (ref "U3") (pin "75") (pinfunction "PA09_75") (pintype "bidirectional"))
    )
    (net (code "22") (name "/PA10") (class "Default")
      (node (ref "R26") (pin "1") (pinfunction "1_1") (pintype "passive"))
      (node (ref "U3") (pin "66") (pinfunction "PA10_66") (pintype "bidirectional"))
    )
    (net (code "23") (name "/PA11") (class "Default")
      (node (ref "R28") (pin "1") (pinfunction "1_1") (pintype "passive"))
      (node (ref "U3") (pin "64") (pinfunction "PA11_64") (pintype "bidirectional"))
    )
    (net (code "24") (name "/PA12") (class "Default")
      (node (ref "R30") (pin "1") (pinfunction "1_1") (pintype "passive"))
      (node (ref "U3") (pin "68") (pinfunction "PA12_68") (pintype "bidirectional"))
    )
    (net (code "25") (name "/PA13") (class "Default")
      (node (ref "R32") (pin "1") (pinfunction "1_1") (pintype "passive"))
      (node (ref "U3") (pin "42") (pinfunction "PA13_42") (pintype "bidirectional"))
    )
    (net (code "26") (name "/PA14") (class "Default")
      (node (ref "R34") (pin "1") (pinfunction "1_1") (pintype "passive"))
      (node (ref "U3") (pin "51") (pinfunction "PA14_51") (pintype "bidirectional"))
    )
    (net (code "27") (name "/PA15") (class "Default")
      (node (ref "R36") (pin "1") (pinfunction "1_1") (pintype "passive"))
      (node (ref "U3") (pin "49") (pinfunction "PA15_49") (pintype "bidirectional"))
    )
    (net (code "28") (name "/PA16") (class "Default")
      (node (ref "R37") (pin "1") (pinfunction "1_1") (pintype "passive"))
      (node (ref "U3") (pin "45") (pinfunction "PA16_45") (pintype "bidirectional"))
    )
    (net (code "29") (name "/PA18") (class "Default")
      (node (ref "R151") (pin "1") (pinfunction "1_1") (pintype "passive"))
      (node (ref "U3") (pin "24") (pinfunction "PA18_24") (pintype "bidirectional"))
    )
    (net (code "30") (name "/PA19") (class "Default")
      (node (ref "C213") (pin "2") (pinfunction "2_2") (pintype "passive"))
      (node (ref "R143") (pin "1") (pinfunction "1_1") (pintype "passive"))
      (node (ref "U3") (pin "23") (pinfunction "PA19_23") (pintype "bidirectional"))
    )
    (net (code "31") (name "/PA20") (class "Default")
      (node (ref "C215") (pin "2") (pinfunction "2_2") (pintype "passive"))
      (node (ref "R150") (pin "1") (pinfunction "1_1") (pintype "passive"))
      (node (ref "U3") (pin "22") (pinfunction "PA20_22") (pintype "bidirectional"))
    )
    (net (code "32") (name "/PA21") (class "Default")
      (node (ref "C224") (pin "2") (pinfunction "2_2") (pintype "passive"))
      (node (ref "R631") (pin "1") (pinfunction "1_1") (pintype "passive"))
      (node (ref "U3") (pin "32") (pinfunction "PA21_32") (pintype "bidirectional"))
    )
    (net (code "33") (name "/PA22") (class "Default")
      (node (ref "R44") (pin "1") (pinfunction "1_1") (pintype "passive"))
      (node (ref "U3") (pin "37") (pinfunction "PA22_37") (pintype "bidirectional"))
    )
    (net (code "34") (name "/PA23") (class "Default")
      (node (ref "R46") (pin "1") (pinfunction "1_1") (pintype "passive"))
      (node (ref "U3") (pin "46") (pinfunction "PA23_46") (pintype "bidirectional"))
    )
    (net (code "35") (name "/PA24") (class "Default")
      (node (ref "R47") (pin "1") (pinfunction "1_1") (pintype "passive"))
      (node (ref "U3") (pin "56") (pinfunction "PA24_56") (pintype "bidirectional"))
    )
    (net (code "36") (name "/PA25") (class "Default")
      (node (ref "R48") (pin "1") (pinfunction "1_1") (pintype "passive"))
      (node (ref "U3") (pin "59") (pinfunction "PA25_59") (pintype "bidirectional"))
    )
    (net (code "37") (name "/PA26") (class "Default")
      (node (ref "R50") (pin "1") (pinfunction "1_1") (pintype "passive"))
      (node (ref "U3") (pin "62") (pinfunction "PA26_62") (pintype "bidirectional"))
    )
    (net (code "38") (name "/PA27") (class "Default")
      (node (ref "R52") (pin "1") (pinfunction "1_1") (pintype "passive"))
      (node (ref "U3") (pin "70") (pinfunction "PA27_70") (pintype "bidirectional"))
    )
    (net (code "39") (name "/PA28") (class "Default")
      (node (ref "R54") (pin "1") (pinfunction "1_1") (pintype "passive"))
      (node (ref "U3") (pin "112") (pinfunction "PA28_112") (pintype "bidirectional"))
    )
    (net (code "40") (name "/PA29") (class "Default")
      (node (ref "R56") (pin "1") (pinfunction "1_1") (pintype "passive"))
      (node (ref "U3") (pin "129") (pinfunction "PA29_129") (pintype "bidirectional"))
    )
    (net (code "41") (name "/PA30") (class "Default")
      (node (ref "R58") (pin "1") (pinfunction "1_1") (pintype "passive"))
      (node (ref "U3") (pin "116") (pinfunction "PA30_116") (pintype "bidirectional"))
    )
    (net (code "42") (name "/PA31") (class "Default")
      (node (ref "R59") (pin "1") (pinfunction "1_1") (pintype "passive"))
      (node (ref "U3") (pin "118") (pinfunction "PA31_118") (pintype "bidirectional"))
    )
    (net (code "43") (name "/PB00") (class "Default")
      (node (ref "C225") (pin "2") (pinfunction "2_2") (pintype "passive"))
      (node (ref "R73") (pin "2") (pinfunction "2_2") (pintype "passive"))
      (node (ref "U3") (pin "21") (pinfunction "PB00_21") (pintype "bidirectional"))
    )
    (net (code "44") (name "/PB01") (class "Default")
      (node (ref "C226") (pin "2") (pinfunction "2_2") (pintype "passive"))
      (node (ref "R75") (pin "2") (pinfunction "2_2") (pintype "passive"))
      (node (ref "U3") (pin "20") (pinfunction "PB01_20") (pintype "bidirectional"))
    )
    (net (code "45") (name "/PB02") (class "Default")
      (node (ref "C227") (pin "2") (pinfunction "2_2") (pintype "passive"))
      (node (ref "R77") (pin "2") (pinfunction "2_2") (pintype "passive"))
      (node (ref "U3") (pin "26") (pinfunction "PB02_26") (pintype "bidirectional"))
    )
    (net (code "46") (name "/PB03") (class "Default")
      (node (ref "C228") (pin "2") (pinfunction "2_2") (pintype "passive"))
      (node (ref "R79") (pin "2") (pinfunction "2_2") (pintype "passive"))
      (node (ref "U3") (pin "31") (pinfunction "PB03_31") (pintype "bidirectional"))
    )
    (net (code "47") (name "/PB04") (class "Default")
      (node (ref "R81") (pin "2") (pinfunction "2_2") (pintype "passive"))
      (node (ref "U3") (pin "105") (pinfunction "PB04_105") (pintype "bidirectional"))
    )
    (net (code "48") (name "/PB05") (class "Default")
      (node (ref "R83") (pin "2") (pinfunction "2_2") (pintype "passive"))
      (node (ref "R86") (pin "2") (pinfunction "2_2") (pintype "passive"))
      (node (ref "U3") (pin "109") (pinfunction "PB05_109") (pintype "bidirectional"))
    )
    (net (code "49") (name "/PB06") (class "Default")
      (node (ref "R85") (pin "2") (pinfunction "2_2") (pintype "passive"))
      (node (ref "U3") (pin "79") (pinfunction "PB06_79") (pintype "bidirectional"))
    )
    (net (code "50") (name "/PB07") (class "Default")
      (node (ref "R88") (pin "2") (pinfunction "2_2") (pintype "passive"))
      (node (ref "U3") (pin "89") (pinfunction "PB07_89") (pintype "bidirectional"))
    )
    (net (code "51") (name "/PB12") (class "Default")
      (node (ref "R94") (pin "2") (pinfunction "2_2") (pintype "passive"))
      (node (ref "U3") (pin "87") (pinfunction "PB12_87") (pintype "bidirectional"))
    )
    (net (code "52") (name "/PB13") (class "Default")
      (node (ref "R621") (pin "2") (pinfunction "2_2") (pintype "passive"))
      (node (ref "U3") (pin "144") (pinfunction "PB13_144") (pintype "bidirectional"))
    )
    (net (code "53") (name "/PC00") (class "Default")
      (node (ref "C217") (pin "2") (pinfunction "2_2") (pintype "passive"))
      (node (ref "R278") (pin "1") (pinfunction "1_1") (pintype "passive"))
      (node (ref "U3") (pin "11") (pinfunction "PC00_11") (pintype "bidirectional"))
    )
    (net (code "54") (name "/PC01") (class "Default")
      (node (ref "R64") (pin "1") (pinfunction "1_1") (pintype "passive"))
      (node (ref "U3") (pin "38") (pinfunction "PC01_38") (pintype "bidirectional"))
    )
    (net (code "55") (name "/PC02") (class "Default")
      (node (ref "R66") (pin "1") (pinfunction "1_1") (pintype "passive"))
      (node (ref "U3") (pin "39") (pinfunction "PC02_39") (pintype "bidirectional"))
    )
    (net (code "56") (name "/PC03") (class "Default")
      (node (ref "R68") (pin "1") (pinfunction "1_1") (pintype "passive"))
      (node (ref "U3") (pin "40") (pinfunction "PC03_40") (pintype "bidirectional"))
    )
    (net (code "57") (name "/PC04") (class "Default")
      (node (ref "R69") (pin "1") (pinfunction "1_1") (pintype "passive"))
      (node (ref "U3") (pin "41") (pinfunction "PC04_41") (pintype "bidirectional"))
    )
    (net (code "58") (name "/PC05") (class "Default")
      (node (ref "R70") (pin "1") (pinfunction "1_1") (pintype "passive"))
      (node (ref "U3") (pin "58") (pinfunction "PC05_58") (pintype "bidirectional"))
    )
    (net (code "59") (name "/PC06") (class "Default")
      (node (ref "R71") (pin "1") (pinfunction "1_1") (pintype "passive"))
      (node (ref "U3") (pin "54") (pinfunction "PC06_54") (pintype "bidirectional"))
    )
    (net (code "60") (name "/PC07") (class "Default")
      (node (ref "R72") (pin "1") (pinfunction "1_1") (pintype "passive"))
      (node (ref "U3") (pin "48") (pinfunction "PC07_48") (pintype "bidirectional"))
    )
    (net (code "61") (name "/PC08") (class "Default")
      (node (ref "R74") (pin "1") (pinfunction "1_1") (pintype "passive"))
      (node (ref "U3") (pin "82") (pinfunction "PC08_82") (pintype "bidirectional"))
    )
    (net (code "62") (name "/PC09") (class "Default")
      (node (ref "R76") (pin "1") (pinfunction "1_1") (pintype "passive"))
      (node (ref "U3") (pin "86") (pinfunction "PC09_86") (pintype "bidirectional"))
    )
    (net (code "63") (name "/PC10") (class "Default")
      (node (ref "R78") (pin "1") (pinfunction "1_1") (pintype "passive"))
      (node (ref "U3") (pin "90") (pinfunction "PC10_90") (pintype "bidirectional"))
    )
    (net (code "64") (name "/PC11") (class "Default")
      (node (ref "R80") (pin "1") (pinfunction "1_1") (pintype "passive"))
      (node (ref "U3") (pin "94") (pinfunction "PC11_94") (pintype "bidirectional"))
    )
    (net (code "65") (name "/PC12") (class "Default")
      (node (ref "R82") (pin "1") (pinfunction "1_1") (pintype "passive"))
      (node (ref "U3") (pin "17") (pinfunction "PC12_17") (pintype "bidirectional"))
    )
    (net (code "66") (name "/PC13") (class "Default")
      (node (ref "C218") (pin "2") (pinfunction "2_2") (pintype "passive"))
      (node (ref "R84") (pin "1") (pinfunction "1_1") (pintype "passive"))
      (node (ref "U3") (pin "19") (pinfunction "PC13_19") (pintype "bidirectional"))
    )
    (net (code "67") (name "/PC14") (class "Default")
      (node (ref "R87") (pin "1") (pinfunction "1_1") (pintype "passive"))
      (node (ref "U3") (pin "97") (pinfunction "PC14_97") (pintype "bidirectional"))
    )
    (net (code "68") (name "/PC15") (class "Default")
      (node (ref "C219") (pin "2") (pinfunction "2_2") (pintype "passive"))
      (node (ref "R89") (pin "1") (pinfunction "1_1") (pintype "passive"))
      (node (ref "U3") (pin "18") (pinfunction "PC15_18") (pintype "bidirectional"))
    )
    (net (code "69") (name "/PC16") (class "Default")
      (node (ref "R91") (pin "1") (pinfunction "1_1") (pintype "passive"))
      (node (ref "U3") (pin "100") (pinfunction "PC16_100") (pintype "bidirectional"))
    )
    (net (code "70") (name "/PC17") (class "Default")
      (node (ref "R93") (pin "1") (pinfunction "1_1") (pintype "passive"))
      (node (ref "U3") (pin "103") (pinfunction "PC17_103") (pintype "bidirectional"))
    )
    (net (code "71") (name "/PC18") (class "Default")
      (node (ref "R95") (pin "1") (pinfunction "1_1") (pintype "passive"))
      (node (ref "U3") (pin "111") (pinfunction "PC18_111") (pintype "bidirectional"))
    )
    (net (code "72") (name "/PC19") (class "Default")
      (node (ref "R622") (pin "1") (pinfunction "1_1") (pintype "passive"))
      (node (ref "U3") (pin "117") (pinfunction "PC19_117") (pintype "bidirectional"))
    )
    (net (code "73") (name "/PC20") (class "Default")
      (node (ref "R98") (pin "1") (pinfunction "1_1") (pintype "passive"))
      (node (ref "U3") (pin "120") (pinfunction "PC20_120") (pintype "bidirectional"))
    )
    (net (code "74") (name "/PC21") (class "Default")
      (node (ref "R99") (pin "1") (pinfunction "1_1") (pintype "passive"))
      (node (ref "U3") (pin "122") (pinfunction "PC21_122") (pintype "bidirectional"))
    )
    (net (code "75") (name "/PC22") (class "Default")
      (node (ref "R100") (pin "1") (pinfunction "1_1") (pintype "passive"))
      (node (ref "U3") (pin "124") (pinfunction "PC22_124") (pintype "bidirectional"))
    )
    (net (code "76") (name "/PC23") (class "Default")
      (node (ref "R101") (pin "1") (pinfunction "1_1") (pintype "passive"))
      (node (ref "U3") (pin "127") (pinfunction "PC23_127") (pintype "bidirectional"))
    )
    (net (code "77") (name "/PC24") (class "Default")
      (node (ref "R102") (pin "1") (pinfunction "1_1") (pintype "passive"))
      (node (ref "U3") (pin "130") (pinfunction "PC24_130") (pintype "bidirectional"))
    )
    (net (code "78") (name "/PC25") (class "Default")
      (node (ref "R286") (pin "1") (pinfunction "1_1") (pintype "passive"))
      (node (ref "U3") (pin "133") (pinfunction "PC25_133") (pintype "bidirectional"))
    )
    (net (code "79") (name "/PC26") (class "Default")
      (node (ref "R103") (pin "1") (pinfunction "1_1") (pintype "passive"))
      (node (ref "U3") (pin "13") (pinfunction "PC26_13") (pintype "bidirectional"))
    )
    (net (code "80") (name "/PC27") (class "Default")
      (node (ref "R104") (pin "1") (pinfunction "1_1") (pintype "passive"))
      (node (ref "U3") (pin "12") (pinfunction "PC27_12") (pintype "bidirectional"))
    )
    (net (code "81") (name "/PC28") (class "Default")
      (node (ref "R105") (pin "1") (pinfunction "1_1") (pintype "passive"))
      (node (ref "U3") (pin "76") (pinfunction "PC28_76") (pintype "bidirectional"))
    )
    (net (code "82") (name "/PC29") (class "Default")
      (node (ref "C220") (pin "2") (pinfunction "2_2") (pintype "passive"))
      (node (ref "R106") (pin "1") (pinfunction "1_1") (pintype "passive"))
      (node (ref "U3") (pin "16") (pinfunction "PC29_16") (pintype "bidirectional"))
    )
    (net (code "83") (name "/PC30") (class "Default")
      (node (ref "C221") (pin "2") (pinfunction "2_2") (pintype "passive"))
      (node (ref "R107") (pin "1") (pinfunction "1_1") (pintype "passive"))
      (node (ref "U3") (pin "15") (pinfunction "PC30_15") (pintype "bidirectional"))
    )
    (net (code "84") (name "/PC31") (class "Default")
      (node (ref "C223") (pin "2") (pinfunction "2_2") (pintype "passive"))
      (node (ref "R108") (pin "1") (pinfunction "1_1") (pintype "passive"))
      (node (ref "U3") (pin "14") (pinfunction "PC31_14") (pintype "bidirectional"))
    )
    (net (code "85") (name "/PD00") (class "Default")
      (node (ref "R12") (pin "2") (pinfunction "2_2") (pintype "passive"))
      (node (ref "U3") (pin "1") (pinfunction "PD00_1") (pintype "bidirectional"))
    )
    (net (code "86") (name "/PD01") (class "Default")
      (node (ref "R613") (pin "2") (pinfunction "2_2") (pintype "passive"))
      (node (ref "U3") (pin "132") (pinfunction "PD01_132") (pintype "bidirectional"))
    )
    (net (code "87") (name "/PD02") (class "Default")
      (node (ref "R16") (pin "2") (pinfunction "2_2") (pintype "passive"))
      (node (ref "U3") (pin "131") (pinfunction "PD02_131") (pintype "bidirectional"))
    )
    (net (code "88") (name "/PD03") (class "Default")
      (node (ref "R18") (pin "2") (pinfunction "2_2") (pintype "passive"))
      (node (ref "U3") (pin "128") (pinfunction "PD03_128") (pintype "bidirectional"))
    )
    (net (code "89") (name "/PD04") (class "Default")
      (node (ref "R19") (pin "2") (pinfunction "2_2") (pintype "passive"))
      (node (ref "U3") (pin "126") (pinfunction "PD04_126") (pintype "bidirectional"))
    )
    (net (code "90") (name "/PD05") (class "Default")
      (node (ref "R21") (pin "2") (pinfunction "2_2") (pintype "passive"))
      (node (ref "U3") (pin "125") (pinfunction "PD05_125") (pintype "bidirectional"))
    )
    (net (code "91") (name "/PD06") (class "Default")
      (node (ref "R23") (pin "2") (pinfunction "2_2") (pintype "passive"))
      (node (ref "U3") (pin "121") (pinfunction "PD06_121") (pintype "bidirectional"))
    )
    (net (code "92") (name "/PD07") (class "Default")
      (node (ref "R616") (pin "2") (pinfunction "2_2") (pintype "passive"))
      (node (ref "U3") (pin "119") (pinfunction "PD07_119") (pintype "bidirectional"))
    )
    (net (code "93") (name "/PD08") (class "Default")
      (node (ref "R312") (pin "2") (pinfunction "2_2") (pintype "passive"))
      (node (ref "U3") (pin "113") (pinfunction "PD08_113") (pintype "bidirectional"))
    )
    (net (code "94") (name "/PD09") (class "Default")
      (node (ref "R25") (pin "2") (pinfunction "2_2") (pintype "passive"))
      (node (ref "U3") (pin "110") (pinfunction "PD09_110") (pintype "bidirectional"))
    )
    (net (code "95") (name "/PD10") (class "Default")
      (node (ref "R27") (pin "2") (pinfunction "2_2") (pintype "passive"))
      (node (ref "U3") (pin "101") (pinfunction "PD10_101") (pintype "bidirectional"))
    )
    (net (code "96") (name "/PD11") (class "Default")
      (node (ref "R29") (pin "2") (pinfunction "2_2") (pintype "passive"))
      (node (ref "U3") (pin "98") (pinfunction "PD11_98") (pintype "bidirectional"))
    )
    (net (code "97") (name "/PD12") (class "Default")
      (node (ref "R31") (pin "2") (pinfunction "2_2") (pintype "passive"))
      (node (ref "U3") (pin "92") (pinfunction "PD12_92") (pintype "bidirectional"))
    )
    (net (code "98") (name "/PD13") (class "Default")
      (node (ref "R33") (pin "2") (pinfunction "2_2") (pintype "passive"))
      (node (ref "U3") (pin "88") (pinfunction "PD13_88") (pintype "bidirectional"))
    )
    (net (code "99") (name "/PD14") (class "Default")
      (node (ref "R617") (pin "2") (pinfunction "2_2") (pintype "passive"))
      (node (ref "U3") (pin "84") (pinfunction "PD14_84") (pintype "bidirectional"))
    )
    (net (code "100") (name "/PD15") (class "Default")
      (node (ref "R131") (pin "2") (pinfunction "2_2") (pintype "passive"))
      (node (ref "U3") (pin "106") (pinfunction "PD15_106") (pintype "bidirectional"))
    )
    (net (code "101") (name "/PD16") (class "Default")
      (node (ref "R133") (pin "2") (pinfunction "2_2") (pintype "passive"))
      (node (ref "U3") (pin "78") (pinfunction "PD16_78") (pintype "bidirectional"))
    )
    (net (code "102") (name "/PD17") (class "Default")
      (node (ref "R39") (pin "2") (pinfunction "2_2") (pintype "passive"))
      (node (ref "U3") (pin "74") (pinfunction "PD17_74") (pintype "bidirectional"))
    )
    (net (code "103") (name "/PD18") (class "Default")
      (node (ref "R618") (pin "2") (pinfunction "2_2") (pintype "passive"))
      (node (ref "U3") (pin "69") (pinfunction "PD18_69") (pintype "bidirectional"))
    )
    (net (code "104") (name "/PD19") (class "Default")
      (node (ref "R41") (pin "1") (pinfunction "1_1") (pintype "passive"))
      (node (ref "U3") (pin "67") (pinfunction "PD19_67") (pintype "bidirectional"))
    )
    (net (code "105") (name "/PD20") (class "Default")
      (node (ref "R42") (pin "2") (pinfunction "2_2") (pintype "passive"))
      (node (ref "U3") (pin "65") (pinfunction "PD20_65") (pintype "bidirectional"))
    )
    (net (code "106") (name "/PD21") (class "Default")
      (node (ref "R43") (pin "2") (pinfunction "2_2") (pintype "passive"))
      (node (ref "U3") (pin "63") (pinfunction "PD21_63") (pintype "bidirectional"))
    )
    (net (code "107") (name "/PD22") (class "Default")
      (node (ref "R45") (pin "2") (pinfunction "2_2") (pintype "passive"))
      (node (ref "U3") (pin "60") (pinfunction "PD22_60") (pintype "bidirectional"))
    )
    (net (code "108") (name "/PD23") (class "Default")
      (node (ref "R126") (pin "2") (pinfunction "2_2") (pintype "passive"))
      (node (ref "U3") (pin "57") (pinfunction "PD23_57") (pintype "bidirectional"))
    )
    (net (code "109") (name "/PD24") (class "Default")
      (node (ref "R127") (pin "2") (pinfunction "2_2") (pintype "passive"))
      (node (ref "U3") (pin "55") (pinfunction "PD24_55") (pintype "bidirectional"))
    )
    (net (code "110") (name "/PD25") (class "Default")
      (node (ref "R49") (pin "2") (pinfunction "2_2") (pintype "passive"))
      (node (ref "U3") (pin "52") (pinfunction "PD25_52") (pintype "bidirectional"))
    )
    (net (code "111") (name "/PD26") (class "Default")
      (node (ref "R51") (pin "2") (pinfunction "2_2") (pintype "passive"))
      (node (ref "U3") (pin "53") (pinfunction "PD26_53") (pintype "bidirectional"))
    )
    (net (code "112") (name "/PD27") (class "Default")
      (node (ref "R53") (pin "2") (pinfunction "2_2") (pintype "passive"))
      (node (ref "U3") (pin "47") (pinfunction "PD27_47") (pintype "bidirectional"))
    )
    (net (code "113") (name "/PD28") (class "Default")
      (node (ref "R55") (pin "2") (pinfunction "2_2") (pintype "passive"))
      (node (ref "U3") (pin "71") (pinfunction "PD28_71") (pintype "bidirectional"))
    )
    (net (code "114") (name "/PD29") (class "Default")
      (node (ref "R57") (pin "1") (pinfunction "1_1") (pintype "passive"))
      (node (ref "U3") (pin "108") (pinfunction "PD29_108") (pintype "bidirectional"))
    )
    (net (code "115") (name "/PD30") (class "Default")
      (node (ref "R277") (pin "1") (pinfunction "1_1") (pintype "passive"))
      (node (ref "U3") (pin "34") (pinfunction "PD30_34") (pintype "bidirectional"))
    )
    (net (code "116") (name "/PD31") (class "Default")
      (node (ref "R650") (pin "1") (pinfunction "1_1") (pintype "passive"))
      (node (ref "U3") (pin "2") (pinfunction "PD31_2") (pintype "bidirectional"))
    )
    (net (code "117") (name "/PE00") (class "Default")
      (node (ref "R619") (pin "2") (pinfunction "2_2") (pintype "passive"))
      (node (ref "U3") (pin "4") (pinfunction "PE00_4") (pintype "bidirectional"))
    )
    (net (code "118") (name "/PE01") (class "Default")
      (node (ref "R65") (pin "2") (pinfunction "2_2") (pintype "passive"))
      (node (ref "U3") (pin "6") (pinfunction "PE01_6") (pintype "bidirectional"))
    )
    (net (code "119") (name "/PE02") (class "Default")
      (node (ref "R67") (pin "2") (pinfunction "2_2") (pintype "passive"))
      (node (ref "U3") (pin "7") (pinfunction "PE02_7") (pintype "bidirectional"))
    )
    (net (code "120") (name "/PE03") (class "Default")
      (node (ref "R281") (pin "2") (pinfunction "2_2") (pintype "passive"))
      (node (ref "U3") (pin "10") (pinfunction "PE03_10") (pintype "bidirectional"))
    )
    (net (code "121") (name "/PE04") (class "Default")
      (node (ref "R282") (pin "2") (pinfunction "2_2") (pintype "passive"))
      (node (ref "U3") (pin "27") (pinfunction "PE04_27") (pintype "bidirectional"))
    )
    (net (code "122") (name "/PE05") (class "Default")
      (node (ref "R620") (pin "2") (pinfunction "2_2") (pintype "passive"))
      (node (ref "U3") (pin "28") (pinfunction "PE05_28") (pintype "bidirectional"))
    )
    (net (code "123") (name "/nSTART") (class "Default")
      (node (ref "R107") (pin "2") (pinfunction "2_2") (pintype "passive"))
    )
    (net (code "124") (name "3.3V_MCU") (class "Default")
      (node (ref "C21") (pin "1") (pinfunction "1_1") (pintype "passive"))
      (node (ref "C23") (pin "2") (pinfunction "2_2") (pintype "passive"))
      (node (ref "C24") (pin "2") (pinfunction "2_2") (pintype "passive"))
      (node (ref "C25") (pin "2") (pinfunction "2_2") (pintype "passive"))
      (node (ref "C26") (pin "2") (pinfunction "2_2") (pintype "passive"))
      (node (ref "C27") (pin "2") (pinfunction "2_2") (pintype "passive"))
      (node (ref "C28") (pin "2") (pinfunction "2_2") (pintype "passive"))
      (node (ref "C29") (pin "2") (pinfunction "2_2") (pintype "passive"))
      (node (ref "C30") (pin "2") (pinfunction "2_2") (pintype "passive"))
      (node (ref "C31") (pin "2") (pinfunction "2_2") (pintype "passive"))
      (node (ref "J3") (pin "2") (pinfunction "2_2") (pintype "passive"))
      (node (ref "R141") (pin "1") (pinfunction "1_1") (pintype "passive"))
      (node (ref "R285") (pin "1") (pinfunction "1_1") (pintype "passive"))
      (node (ref "R61") (pin "2") (pinfunction "2_2") (pintype "passive"))
      (node (ref "U3") (pin "134") (pinfunction "VDDUTMII_134") (pintype "power_in"))
      (node (ref "U3") (pin "143") (pinfunction "VDDPLLUSB_143") (pintype "power_in"))
      (node (ref "U3") (pin "30") (pinfunction "VDDIO_30") (pintype "power_in"))
      (node (ref "U3") (pin "43") (pinfunction "VDDIO_43") (pintype "power_in"))
      (node (ref "U3") (pin "5") (pinfunction "VDDIN_5") (pintype "power_in"))
      (node (ref "U3") (pin "72") (pinfunction "VDDIO_72") (pintype "power_in"))
      (node (ref "U3") (pin "80") (pinfunction "VDDIO_80") (pintype "power_in"))
      (node (ref "U3") (pin "9") (pinfunction "ADVREFP_9") (pintype "power_in"))
      (node (ref "U3") (pin "96") (pinfunction "VDDIO_96") (pintype "power_in"))
    )
    (net (code "125") (name "ADC_SWITCH") (class "Default")
      (node (ref "R79") (pin "1") (pinfunction "1_1") (pintype "passive"))
    )
    (net (code "126") (name "ADC_TEMP1") (class "Default")
      (node (ref "R143") (pin "2") (pinfunction "2_2") (pintype "passive"))
    )
    (net (code "127") (name "ADC_TEMP2") (class "Default")
      (node (ref "R150") (pin "2") (pinfunction "2_2") (pintype "passive"))
    )
    (net (code "128") (name "ADC_TEMP3") (class "Default")
      (node (ref "R108") (pin "2") (pinfunction "2_2") (pintype "passive"))
    )
    (net (code "129") (name "ADC_TEMP4") (class "Default")
      (node (ref "R75") (pin "1") (pinfunction "1_1") (pintype "passive"))
    )
    (net (code "130") (name "ADC_TEMP5") (class "Default")
      (node (ref "R89") (pin "2") (pinfunction "2_2") (pintype "passive"))
    )
    (net (code "131") (name "ADC_TEMP6") (class "Default")
      (node (ref "R84") (pin "2") (pinfunction "2_2") (pintype "passive"))
    )
    (net (code "132") (name "ADC_TEMP7") (class "Default")
      (node (ref "R278") (pin "2") (pinfunction "2_2") (pintype "passive"))
    )
    (net (code "133") (name "ADC_TEMP8") (class "Default")
      (node (ref "R106") (pin "2") (pinfunction "2_2") (pintype "passive"))
    )
    (net (code "134") (name "ADC_TEMP_SENSOR") (class "Default")
      (node (ref "R281") (pin "1") (pinfunction "1_1") (pintype "passive"))
    )
    (net (code "135") (name "ADT2_USB_D_N") (class "Default")
      (node (ref "U3") (pin "136") (pinfunction "HSDM_136") (pintype "bidirectional"))
    )
    (net (code "136") (name "ADT2_USB_D_P") (class "Default")
      (node (ref "U3") (pin "137") (pinfunction "HSDP_137") (pintype "bidirectional"))
    )
    (net (code "137") (name "CANRX1") (class "Default")
      (node (ref "R82") (pin "2") (pinfunction "2_2") (pintype "passive"))
    )
    (net (code "138") (name "CANTX1") (class "Default")
      (node (ref "R87") (pin "2") (pinfunction "2_2") (pintype "passive"))
    )
    (net (code "139") (name "CPU_MCU_SPI_CS") (class "Default")
      (node (ref "R286") (pin "2") (pinfunction "2_2") (pintype "passive"))
    )
    (net (code "140") (name "GND") (class "Default")
      (node (ref "C15") (pin "1") (pinfunction "1_1") (pintype "passive"))
      (node (ref "C18") (pin "1") (pinfunction "1_1") (pintype "passive"))
      (node (ref "C19") (pin "1") (pinfunction "1_1") (pintype "passive"))
      (node (ref "C20") (pin "1") (pinfunction "1_1") (pintype "passive"))
      (node (ref "C21") (pin "2") (pinfunction "2_2") (pintype "passive"))
      (node (ref "C213") (pin "1") (pinfunction "1_1") (pintype "passive"))
      (node (ref "C215") (pin "1") (pinfunction "1_1") (pintype "passive"))
      (node (ref "C217") (pin "1") (pinfunction "1_1") (pintype "passive"))
      (node (ref "C218") (pin "1") (pinfunction "1_1") (pintype "passive"))
      (node (ref "C219") (pin "1") (pinfunction "1_1") (pintype "passive"))
      (node (ref "C22") (pin "2") (pinfunction "2_2") (pintype "passive"))
      (node (ref "C220") (pin "1") (pinfunction "1_1") (pintype "passive"))
      (node (ref "C221") (pin "1") (pinfunction "1_1") (pintype "passive"))
      (node (ref "C223") (pin "1") (pinfunction "1_1") (pintype "passive"))
      (node (ref "C224") (pin "1") (pinfunction "1_1") (pintype "passive"))
      (node (ref "C225") (pin "1") (pinfunction "1_1") (pintype "passive"))
      (node (ref "C226") (pin "1") (pinfunction "1_1") (pintype "passive"))
      (node (ref "C227") (pin "1") (pinfunction "1_1") (pintype "passive"))
      (node (ref "C228") (pin "1") (pinfunction "1_1") (pintype "passive"))
      (node (ref "C23") (pin "1") (pinfunction "1_1") (pintype "passive"))
      (node (ref "C24") (pin "1") (pinfunction "1_1") (pintype "passive"))
      (node (ref "C25") (pin "1") (pinfunction "1_1") (pintype "passive"))
      (node (ref "C26") (pin "1") (pinfunction "1_1") (pintype "passive"))
      (node (ref "C27") (pin "1") (pinfunction "1_1") (pintype "passive"))
      (node (ref "C28") (pin "1") (pinfunction "1_1") (pintype "passive"))
      (node (ref "C29") (pin "1") (pinfunction "1_1") (pintype "passive"))
      (node (ref "C30") (pin "1") (pinfunction "1_1") (pintype "passive"))
      (node (ref "C31") (pin "1") (pinfunction "1_1") (pintype "passive"))
      (node (ref "C32") (pin "1") (pinfunction "1_1") (pintype "passive"))
      (node (ref "C33") (pin "1") (pinfunction "1_1") (pintype "passive"))
      (node (ref "C34") (pin "1") (pinfunction "1_1") (pintype "passive"))
      (node (ref "C35") (pin "1") (pinfunction "1_1") (pintype "passive"))
      (node (ref "C36") (pin "1") (pinfunction "1_1") (pintype "passive"))
      (node (ref "C37") (pin "1") (pinfunction "1_1") (pintype "passive"))
      (node (ref "C38") (pin "1") (pinfunction "1_1") (pintype "passive"))
      (node (ref "C39") (pin "1") (pinfunction "1_1") (pintype "passive"))
      (node (ref "J3") (pin "3") (pinfunction "3_3") (pintype "passive"))
      (node (ref "R110") (pin "1") (pinfunction "1_1") (pintype "passive"))
      (node (ref "R298") (pin "2") (pinfunction "2_2") (pintype "passive"))
      (node (ref "U3") (pin "115") (pinfunction "GND_115") (pintype "power_in"))
      (node (ref "U3") (pin "135") (pinfunction "GND_135") (pintype "power_in"))
      (node (ref "U3") (pin "138") (pinfunction "GND_138") (pintype "power_in"))
      (node (ref "U3") (pin "44") (pinfunction "GND_44") (pintype "power_in"))
      (node (ref "U3") (pin "61") (pinfunction "GND_61") (pintype "power_in"))
      (node (ref "U3") (pin "8") (pinfunction "ADVREFN_8") (pintype "power_in"))
      (node (ref "U3") (pin "95") (pinfunction "GND_95") (pintype "power_in"))
      (node (ref "XC2") (pin "2") (pinfunction "2_2") (pintype "passive"))
      (node (ref "XC2") (pin "4") (pinfunction "4_4") (pintype "passive"))
    )
    (net (code "141") (name "HEATER_PWM_1") (class "Default")
      (node (ref "R52") (pin "2") (pinfunction "2_2") (pintype "passive"))
    )
    (net (code "142") (name "HEATER_PWM_2") (class "Default")
      (node (ref "R11") (pin "2") (pinfunction "2_2") (pintype "passive"))
    )
    (net (code "143") (name "HEATER_PWM_3") (class "Default")
      (node (ref "R13") (pin "2") (pinfunction "2_2") (pintype "passive"))
    )
    (net (code "144") (name "HEATER_PWM_4") (class "Default")
      (node (ref "R50") (pin "2") (pinfunction "2_2") (pintype "passive"))
    )
    (net (code "145") (name "HEATER_PWM_5") (class "Default")
      (node (ref "R74") (pin "2") (pinfunction "2_2") (pintype "passive"))
    )
    (net (code "146") (name "HEATER_PWM_6") (class "Default")
      (node (ref "R101") (pin "2") (pinfunction "2_2") (pintype "passive"))
    )
    (net (code "147") (name "HEATER_PWM_7") (class "Default")
      (node (ref "R70") (pin "2") (pinfunction "2_2") (pintype "passive"))
    )
    (net (code "148") (name "HEATER_PWM_8") (class "Default")
      (node (ref "R71") (pin "2") (pinfunction "2_2") (pintype "passive"))
    )
    (net (code "149") (name "IF_MCU_SHUTDOWN") (class "Default")
      (node (ref "R312") (pin "1") (pinfunction "1_1") (pintype "passive"))
    )
    (net (code "150") (name "LASER_ADC_1") (class "Default")
      (node (ref "R73") (pin "1") (pinfunction "1_1") (pintype "passive"))
    )
    (net (code "151") (name "LASER_ADC_2") (class "Default")
      (node (ref "R77") (pin "1") (pinfunction "1_1") (pintype "passive"))
    )
    (net (code "153") (name "LASER_DAC_LATCH") (class "Default")
      (node (ref "R91") (pin "2") (pinfunction "2_2") (pintype "passive"))
    )
    (net (code "154") (name "LASER_SPI_nCS1") (class "Default")
      (node (ref "R59") (pin "2") (pinfunction "2_2") (pintype "passive"))
    )
    (net (code "155") (name "LASER_SW_EXT_CS") (class "Default")
      (node (ref "R37") (pin "2") (pinfunction "2_2") (pintype "passive"))
    )
    (net (code "156") (name "LASER_SW_INT_CS") (class "Default")
      (node (ref "R72") (pin "2") (pinfunction "2_2") (pintype "passive"))
    )
    (net (code "157") (name "LSM6DSOX_INT") (class "Default")
      (node (ref "R99") (pin "2") (pinfunction "2_2") (pintype "passive"))
    )
    (net (code "158") (name "MCU_CONSOLE_RX") (class "Default")
      (node (ref "R49") (pin "1") (pinfunction "1_1") (pintype "passive"))
    )
    (net (code "159") (name "MCU_CONSOLE_TX") (class "Default")
      (node (ref "R51") (pin "1") (pinfunction "1_1") (pintype "passive"))
    )
    (net (code "160") (name "MCU_FRAM_nCS") (class "Default")
      (node (ref "R41") (pin "2") (pinfunction "2_2") (pintype "passive"))
    )
    (net (code "161") (name "MCU_HD4_I2C2_SCL") (class "Default")
      (node (ref "R55") (pin "1") (pinfunction "1_1") (pintype "passive"))
    )
    (net (code "162") (name "MCU_HD4_I2C2_SDA") (class "Default")
      (node (ref "R53") (pin "1") (pinfunction "1_1") (pintype "passive"))
    )
    (net (code "163") (name "MCU_HD4_I2C_EN") (class "Default")
      (node (ref "R93") (pin "2") (pinfunction "2_2") (pintype "passive"))
    )
    (net (code "164") (name "MCU_I2C0_SCL") (class "Default")
      (node (ref "R20") (pin "2") (pinfunction "2_2") (pintype "passive"))
    )
    (net (code "165") (name "MCU_I2C0_SDA") (class "Default")
      (node (ref "R17") (pin "2") (pinfunction "2_2") (pintype "passive"))
    )
    (net (code "166") (name "MCU_I2C1_SCL") (class "Default")
      (node (ref "R86") (pin "1") (pinfunction "1_1") (pintype "passive"))
    )
    (net (code "167") (name "MCU_I2C1_SDA") (class "Default")
      (node (ref "R81") (pin "1") (pinfunction "1_1") (pintype "passive"))
    )
    (net (code "168") (name "MCU_LASER_QSPI_MISO") (class "Default")
      (node (ref "R524") (pin "2") (pinfunction "2_2") (pintype "passive"))
    )
    (net (code "169") (name "MCU_LASER_QSPI_MOSI") (class "Default")
      (node (ref "R458") (pin "2") (pinfunction "2_2") (pintype "passive"))
    )
    (net (code "170") (name "MCU_LASER_QSPI_SCK") (class "Default")
      (node (ref "R632") (pin "2") (pinfunction "2_2") (pintype "passive"))
    )
    (net (code "171") (name "MCU_MRAM_QSPI_CLK") (class "Default")
      (node (ref "R34") (pin "2") (pinfunction "2_2") (pintype "passive"))
      (node (ref "R632") (pin "1") (pinfunction "1_1") (pintype "passive"))
    )
    (net (code "172") (name "MCU_MRAM_QSPI_IO0") (class "Default")
      (node (ref "R32") (pin "2") (pinfunction "2_2") (pintype "passive"))
      (node (ref "R458") (pin "1") (pinfunction "1_1") (pintype "passive"))
    )
    (net (code "173") (name "MCU_MRAM_QSPI_IO1") (class "Default")
      (node (ref "R30") (pin "2") (pinfunction "2_2") (pintype "passive"))
      (node (ref "R524") (pin "1") (pinfunction "1_1") (pintype "passive"))
    )
    (net (code "174") (name "MCU_PRAM_SPI1_nCS") (class "Default")
      (node (ref "R105") (pin "2") (pinfunction "2_2") (pintype "passive"))
    )
    (net (code "175") (name "MCU_PRAM_SW_SEL") (class "Default")
      (node (ref "R457") (pin "2") (pinfunction "2_2") (pintype "passive"))
    )
    (net (code "176") (name "MCU_RAM_QSPI_nCS") (class "Default")
      (node (ref "R28") (pin "2") (pinfunction "2_2") (pintype "passive"))
    )
    (net (code "177") (name "MCU_RTC_CLKOUT") (class "Default")
      (node (ref "R68") (pin "2") (pinfunction "2_2") (pintype "passive"))
    )
    (net (code "178") (name "MCU_RTC_INT") (class "Default")
      (node (ref "R69") (pin "2") (pinfunction "2_2") (pintype "passive"))
    )
    (net (code "179") (name "MCU_SENSOR1_nIRQ") (class "Default")
      (node (ref "R126") (pin "1") (pinfunction "1_1") (pintype "passive"))
    )
    (net (code "180") (name "MCU_SENSOR2_nIRQ") (class "Default")
      (node (ref "R127") (pin "1") (pinfunction "1_1") (pintype "passive"))
    )
    (net (code "181") (name "MCU_SENSOR3_nIRQ") (class "Default")
      (node (ref "R57") (pin "2") (pinfunction "2_2") (pintype "passive"))
    )
    (net (code "182") (name "MCU_SENSOR4_nIRQ") (class "Default")
      (node (ref "R277") (pin "2") (pinfunction "2_2") (pintype "passive"))
    )
    (net (code "183") (name "MCU_SOM_GPIO_A") (class "Default")
      (node (ref "R25") (pin "1") (pinfunction "1_1") (pintype "passive"))
    )
    (net (code "184") (name "MCU_SOM_GPIO_B") (class "Default")
      (node (ref "R27") (pin "1") (pinfunction "1_1") (pintype "passive"))
    )
    (net (code "185") (name "MCU_SPI0_CMD_SOLE_A") (class "Default")
      (node (ref "R622") (pin "2") (pinfunction "2_2") (pintype "passive"))
    )
    (net (code "186") (name "MCU_SPI0_CMD_SOLE_B") (class "Default")
      (node (ref "R620") (pin "1") (pinfunction "1_1") (pintype "passive"))
    )
    (net (code "187") (name "MCU_SPI0_CMD_SOLE_C") (class "Default")
      (node (ref "R617") (pin "1") (pinfunction "1_1") (pintype "passive"))
    )
    (net (code "188") (name "MCU_SPI0_CMD_SOLE_D") (class "Default")
      (node (ref "R616") (pin "1") (pinfunction "1_1") (pintype "passive"))
    )
    (net (code "189") (name "MCU_SPI0_CMD_SOLE_E") (class "Default")
      (node (ref "R615") (pin "2") (pinfunction "2_2") (pintype "passive"))
    )
    (net (code "190") (name "MCU_SPI0_MISO") (class "Default")
      (node (ref "R141") (pin "2") (pinfunction "2_2") (pintype "passive"))
      (node (ref "R42") (pin "1") (pinfunction "1_1") (pintype "passive"))
    )
    (net (code "191") (name "MCU_SPI0_MOSI") (class "Default")
      (node (ref "R43") (pin "1") (pinfunction "1_1") (pintype "passive"))
    )
    (net (code "192") (name "MCU_SPI0_SCK") (class "Default")
      (node (ref "R45") (pin "1") (pinfunction "1_1") (pintype "passive"))
    )
    (net (code "193") (name "MCU_SPI0_nCS_SOLE_A") (class "Default")
      (node (ref "R621") (pin "1") (pinfunction "1_1") (pintype "passive"))
    )
    (net (code "194") (name "MCU_SPI0_nCS_SOLE_B") (class "Default")
      (node (ref "R619") (pin "1") (pinfunction "1_1") (pintype "passive"))
    )
    (net (code "195") (name "MCU_SPI0_nCS_SOLE_C") (class "Default")
      (node (ref "R613") (pin "1") (pinfunction "1_1") (pintype "passive"))
    )
    (net (code "196") (name "MCU_SPI0_nCS_SOLE_D") (class "Default")
      (node (ref "R618") (pin "1") (pinfunction "1_1") (pintype "passive"))
    )
    (net (code "197") (name "MCU_SPI0_nCS_SOLE_E") (class "Default")
      (node (ref "R614") (pin "2") (pinfunction "2_2") (pintype "passive"))
    )
    (net (code "198") (name "MCU_SPI1_MISO") (class "Default")
      (node (ref "R103") (pin "2") (pinfunction "2_2") (pintype "passive"))
      (node (ref "R285") (pin "2") (pinfunction "2_2") (pintype "passive"))
    )
    (net (code "199") (name "MCU_SPI1_MOSI") (class "Default")
      (node (ref "R104") (pin "2") (pinfunction "2_2") (pintype "passive"))
    )
    (net (code "200") (name "MCU_SPI1_SCK") (class "Default")
      (node (ref "R102") (pin "2") (pinfunction "2_2") (pintype "passive"))
    )
    (net (code "201") (name "MCU_STATUS_LED_1") (class "Default")
      (node (ref "D36") (pin "2") (pinfunction "A_2") (pintype "passive"))
      (node (ref "R94") (pin "1") (pinfunction "1_1") (pintype "passive"))
    )
    (net (code "202") (name "MCU_UART0_RX_SOM_TX") (class "Default")
      (node (ref "R24") (pin "2") (pinfunction "2_2") (pintype "passive"))
    )
    (net (code "203") (name "MCU_UART0_TX_SOM_RX") (class "Default")
      (node (ref "R26") (pin "2") (pinfunction "2_2") (pintype "passive"))
    )
    (net (code "204") (name "MCU_USART_RXD2") (class "Default")
      (node (ref "R131") (pin "1") (pinfunction "1_1") (pintype "passive"))
    )
    (net (code "205") (name "MCU_USART_SCK2") (class "Default")
      (node (ref "R39") (pin "1") (pinfunction "1_1") (pintype "passive"))
    )
    (net (code "206") (name "MCU_USART_TXD2") (class "Default")
      (node (ref "R133") (pin "1") (pinfunction "1_1") (pintype "passive"))
    )
    (net (code "207") (name "MCU_WD_DONE") (class "Default")
      (node (ref "R65") (pin "1") (pinfunction "1_1") (pintype "passive"))
    )
    (net (code "208") (name "MCU_WD_WAKE") (class "Default")
      (node (ref "R67") (pin "1") (pinfunction "1_1") (pintype "passive"))
    )
    (net (code "209") (name "MCU_WD_nRESET") (class "Default")
      (node (ref "R303") (pin "2") (pinfunction "2_2") (pintype "passive"))
    )
    (net (code "210") (name "Net-(C15-Pad2)") (class "Default")
      (node (ref "C15") (pin "2") (pinfunction "2_2") (pintype "passive"))
      (node (ref "R303") (pin "1") (pinfunction "1_1") (pintype "passive"))
      (node (ref "R61") (pin "1") (pinfunction "1_1") (pintype "passive"))
      (node (ref "R63") (pin "2") (pinfunction "2_2") (pintype "passive"))
    )
    (net (code "211") (name "Net-(D36-K)") (class "Default")
      (node (ref "D36") (pin "1") (pinfunction "K_1") (pintype "passive"))
      (node (ref "R298") (pin "1") (pinfunction "1_1") (pintype "passive"))
    )
    (net (code "212") (name "Net-(U3-VBG)") (class "Default")
      (node (ref "C18") (pin "2") (pinfunction "2_2") (pintype "passive"))
      (node (ref "R110") (pin "2") (pinfunction "2_2") (pintype "passive"))
      (node (ref "U3") (pin "140") (pinfunction "VBG_140") (pintype "power_in"))
    )
    (net (code "213") (name "PHOTO_ADC_CONV") (class "Default")
      (node (ref "R36") (pin "2") (pinfunction "2_2") (pintype "passive"))
    )
    (net (code "214") (name "PHOTO_ADC_CS") (class "Default")
      (node (ref "R12") (pin "1") (pinfunction "1_1") (pintype "passive"))
    )
    (net (code "215") (name "PHOTO_ADC_EOC") (class "Default")
      (node (ref "R151") (pin "2") (pinfunction "2_2") (pintype "passive"))
    )
    (net (code "217") (name "PHOTO_SPI0_nCS2") (class "Default")
      (node (ref "R31") (pin "1") (pinfunction "1_1") (pintype "passive"))
    )
    (net (code "218") (name "POW_ONOFF_AI") (class "Default")
      (node (ref "R624") (pin "2") (pinfunction "2_2") (pintype "passive"))
    )
    (net (code "219") (name "POW_ONOFF_BUCK_PERI") (class "Default")
      (node (ref "R282") (pin "1") (pinfunction "1_1") (pintype "passive"))
    )
    (net (code "220") (name "POW_ONOFF_HD4") (class "Default")
      (node (ref "R18") (pin "1") (pinfunction "1_1") (pintype "passive"))
    )
    (net (code "221") (name "POW_ONOFF_HEATER") (class "Default")
      (node (ref "R280") (pin "2") (pinfunction "2_2") (pintype "passive"))
    )
    (net (code "222") (name "POW_ONOFF_LP") (class "Default")
      (node (ref "R23") (pin "1") (pinfunction "1_1") (pintype "passive"))
    )
    (net (code "223") (name "POW_ONOFF_SOM") (class "Default")
      (node (ref "R21") (pin "1") (pinfunction "1_1") (pintype "passive"))
    )
    (net (code "224") (name "POW_ONOFF_Solenoid") (class "Default")
      (node (ref "R16") (pin "1") (pinfunction "1_1") (pintype "passive"))
    )
    (net (code "225") (name "POW_ONOFF_TEC") (class "Default")
      (node (ref "R19") (pin "1") (pinfunction "1_1") (pintype "passive"))
    )
    (net (code "226") (name "SENSOR1_EN") (class "Default")
      (node (ref "R76") (pin "2") (pinfunction "2_2") (pintype "passive"))
    )
    (net (code "227") (name "SENSOR2_EN") (class "Default")
      (node (ref "R78") (pin "2") (pinfunction "2_2") (pintype "passive"))
    )
    (net (code "228") (name "SENSOR3_EN") (class "Default")
      (node (ref "R54") (pin "2") (pinfunction "2_2") (pintype "passive"))
    )
    (net (code "229") (name "SENSOR4_EN") (class "Default")
      (node (ref "R56") (pin "2") (pinfunction "2_2") (pintype "passive"))
    )
    (net (code "230") (name "SENSOR5_EN") (class "Default")
      (node (ref "R80") (pin "2") (pinfunction "2_2") (pintype "passive"))
    )
    (net (code "231") (name "SOLENOID_CTR_1") (class "Default")
      (node (ref "R44") (pin "2") (pinfunction "2_2") (pintype "passive"))
    )
    (net (code "232") (name "SOLENOID_CTR_2") (class "Default")
      (node (ref "R46") (pin "2") (pinfunction "2_2") (pintype "passive"))
    )
    (net (code "233") (name "SOLENOID_CTR_3") (class "Default")
      (node (ref "R47") (pin "2") (pinfunction "2_2") (pintype "passive"))
    )
    (net (code "234") (name "SOLENOID_CTR_4") (class "Default")
      (node (ref "R48") (pin "2") (pinfunction "2_2") (pintype "passive"))
    )
    (net (code "235") (name "TEC_SWEN_1") (class "Default")
      (node (ref "R58") (pin "2") (pinfunction "2_2") (pintype "passive"))
    )
    (net (code "236") (name "TEC_SWEN_2") (class "Default")
      (node (ref "R33") (pin "1") (pinfunction "1_1") (pintype "passive"))
    )
    (net (code "237") (name "TEC_SWEN_3") (class "Default")
      (node (ref "R64") (pin "2") (pinfunction "2_2") (pintype "passive"))
    )
    (net (code "238") (name "TEC_SWEN_4") (class "Default")
      (node (ref "R66") (pin "2") (pinfunction "2_2") (pintype "passive"))
    )
    (net (code "239") (name "TEC_nCS_1") (class "Default")
      (node (ref "R95") (pin "2") (pinfunction "2_2") (pintype "passive"))
    )
    (net (code "240") (name "TEC_nCS_2") (class "Default")
      (node (ref "R98") (pin "2") (pinfunction "2_2") (pintype "passive"))
    )
    (net (code "241") (name "TEC_nCS_3") (class "Default")
      (node (ref "R100") (pin "2") (pinfunction "2_2") (pintype "passive"))
    )
    (net (code "242") (name "TEC_nCS_4") (class "Default")
      (node (ref "R29") (pin "1") (pinfunction "1_1") (pintype "passive"))
    )
    (net (code "245") (name "unconnected-(J3-Pad1)") (class "Default")
      (node (ref "J3") (pin "1") (pinfunction "1_1") (pintype "passive"))
    )
    (net (code "246") (name "unconnected-(J3-Pad7)") (class "Default")
      (node (ref "J3") (pin "7") (pinfunction "7_7") (pintype "passive"))
    )
    (net (code "247") (name "unconnected-(U3-PA17-Pad25)") (class "Default")
      (node (ref "U3") (pin "25") (pinfunction "PA17_25") (pintype "bidirectional+no_connect"))
    )
  )
)
